# microDriver_v2.net
KiCad netlist of a schematic drawn in EAGLE
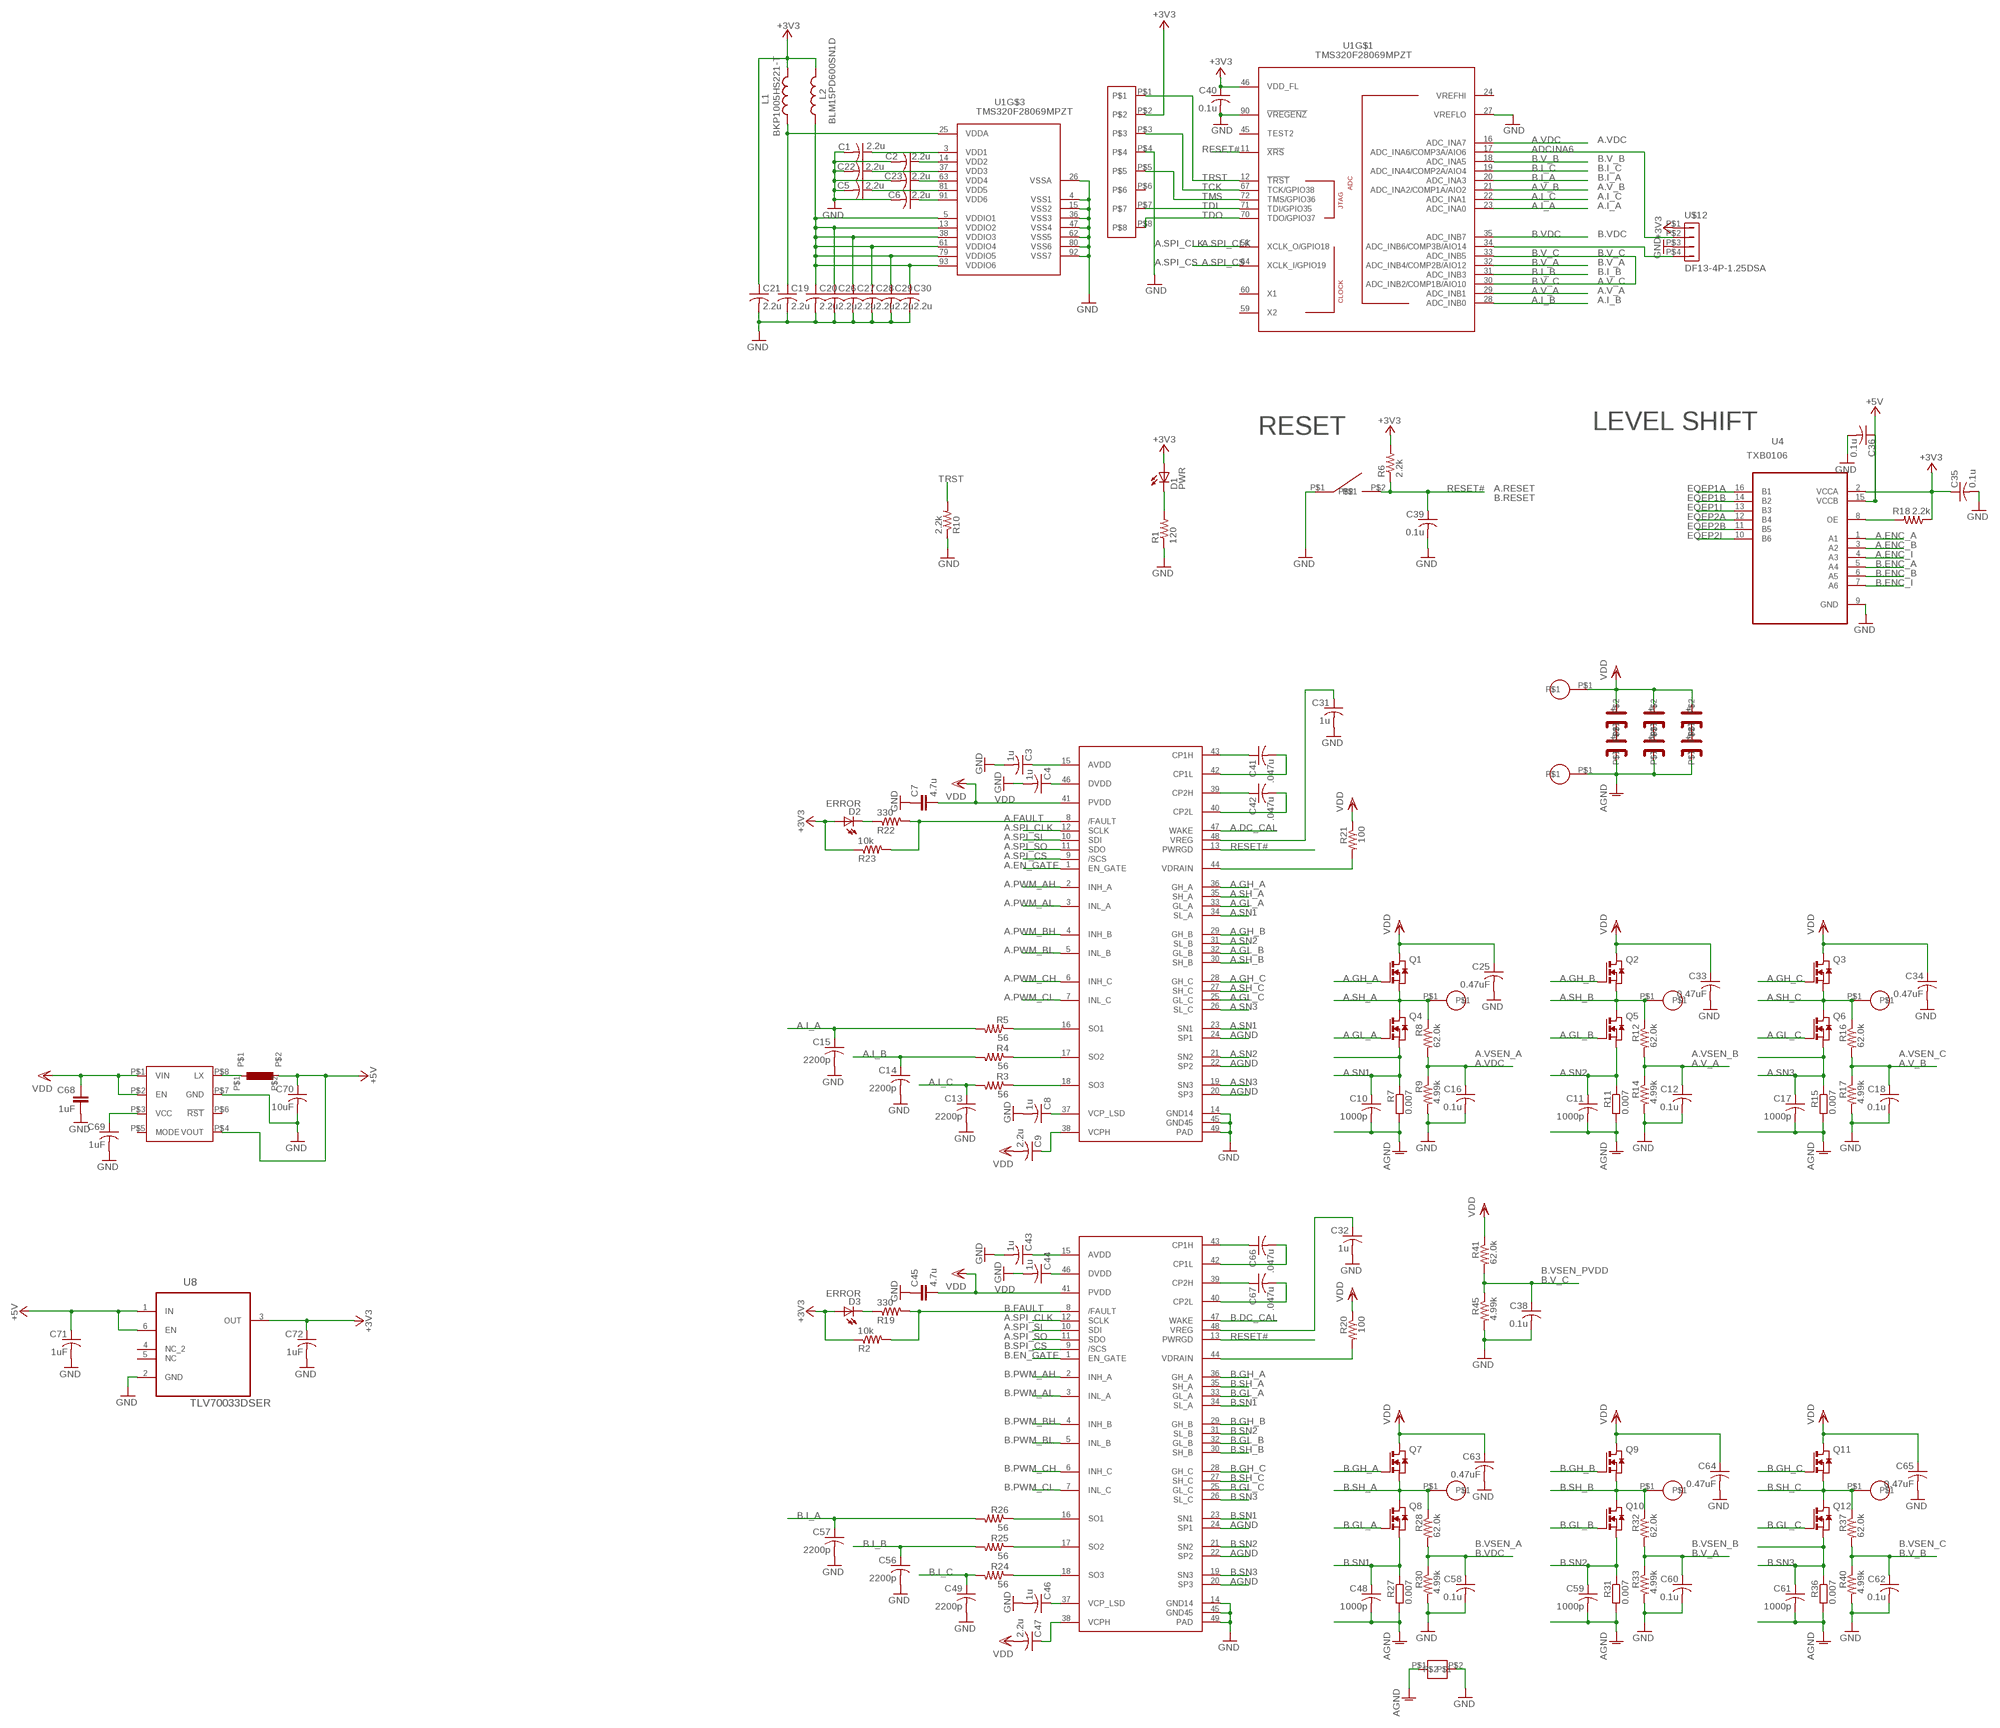
[diagram p0: schematic, sheet 1]
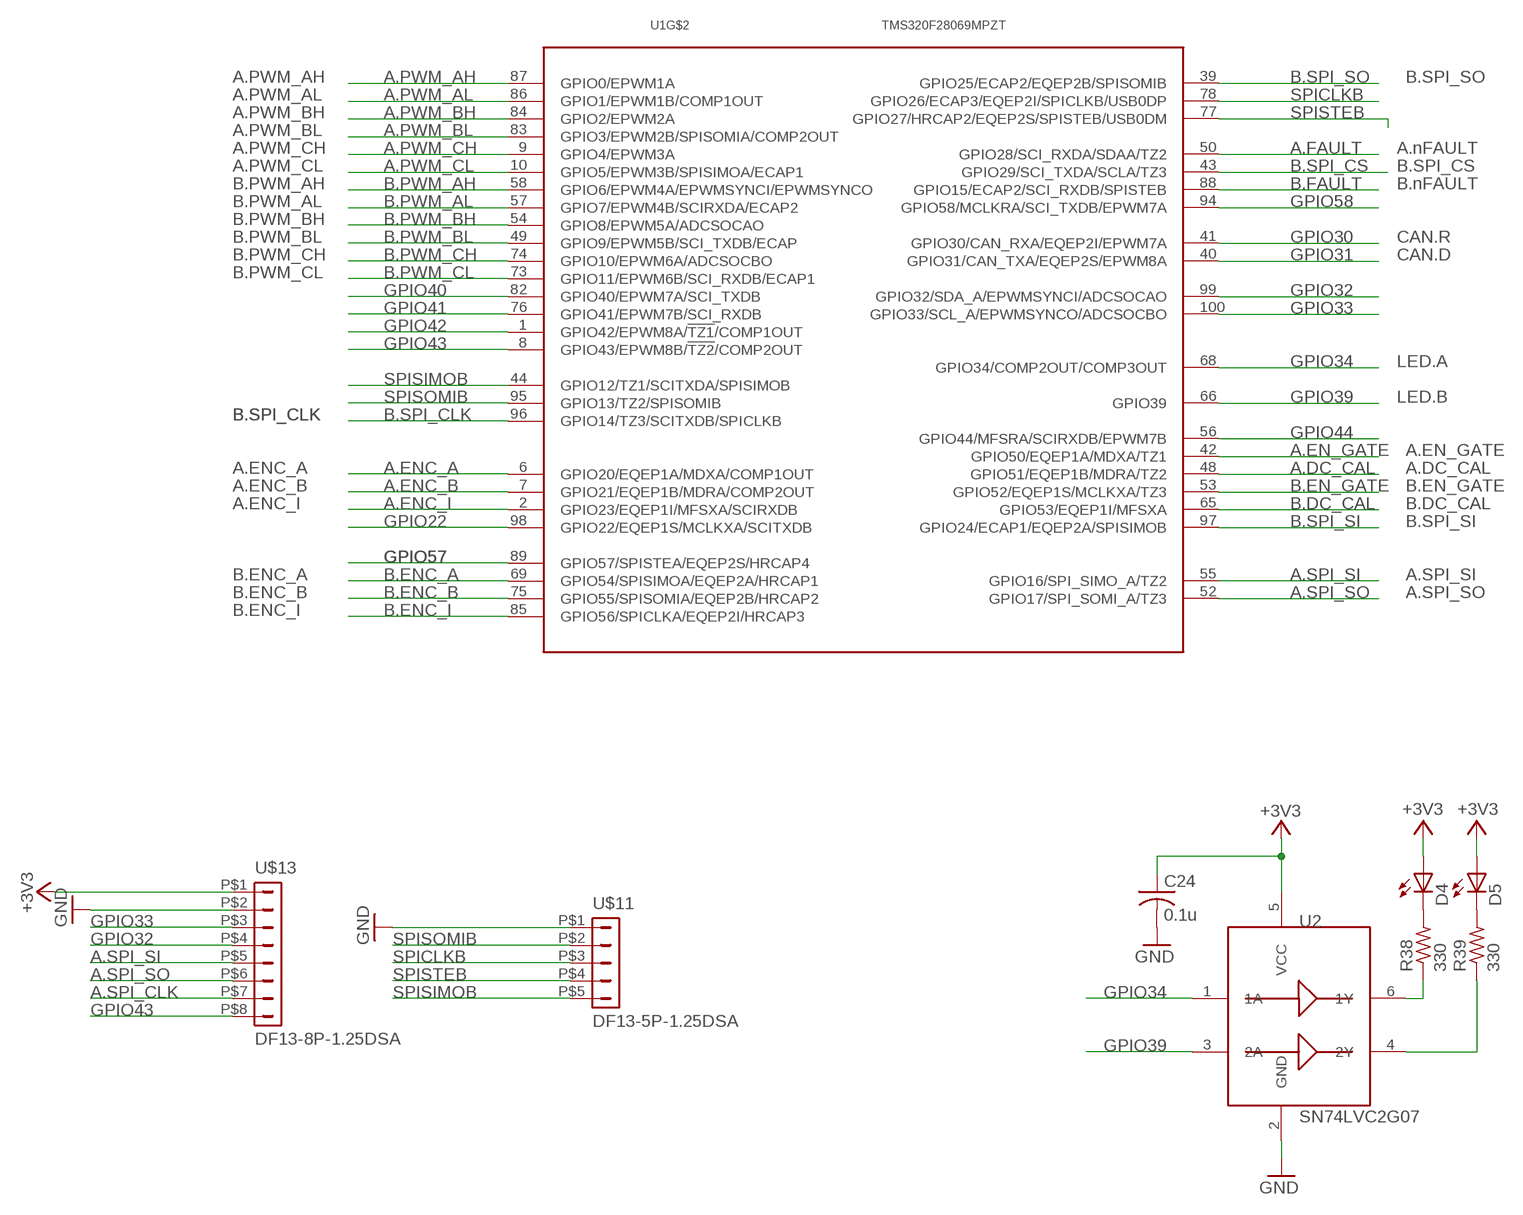
[diagram p1: schematic, sheet 2]
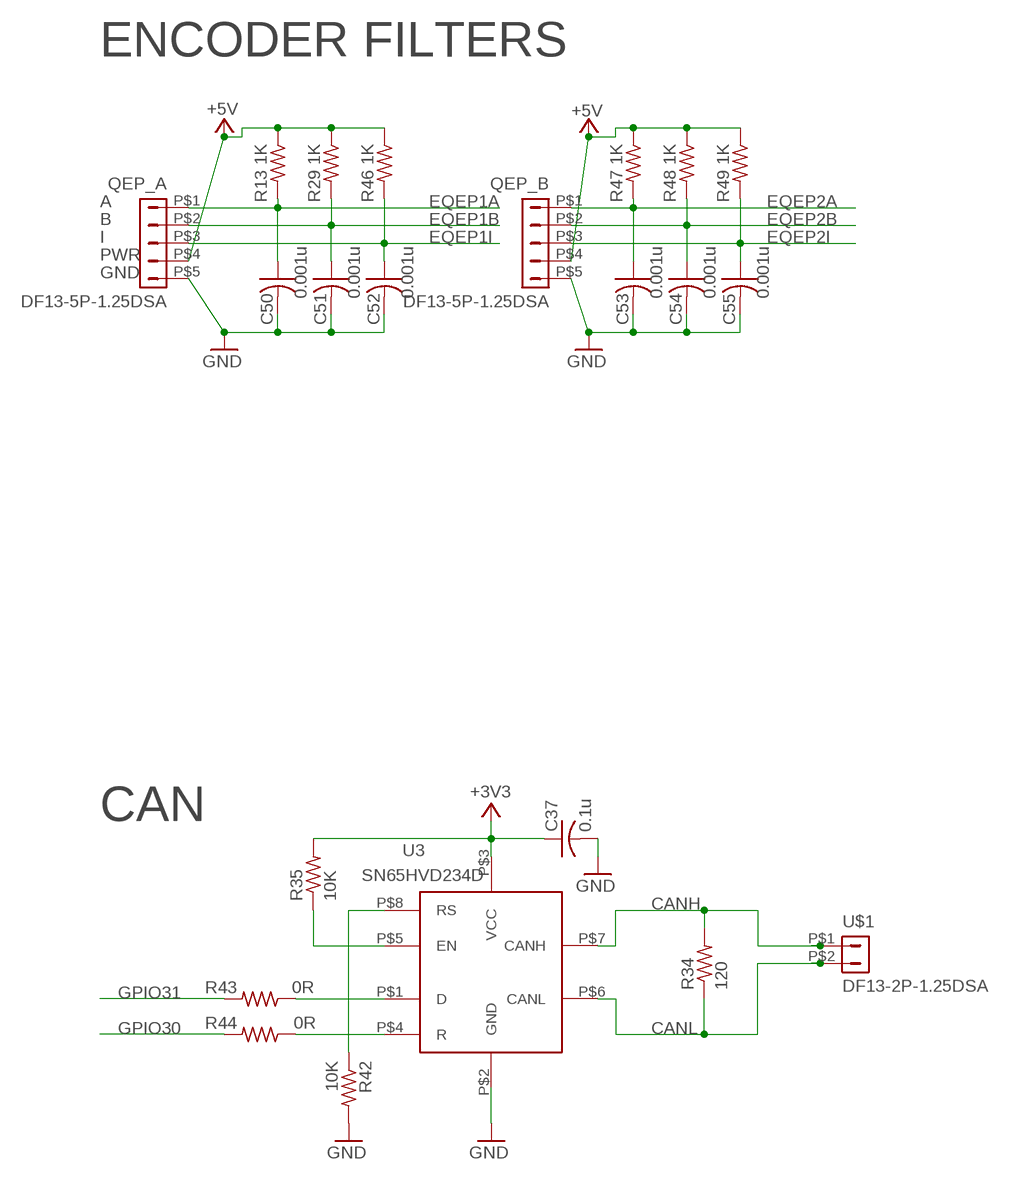
[diagram p2: schematic, sheet 3]

(export (version "E")
  (design (tool "Eeschema 10.0.6"))
  (components
    (comp (ref "C37")
      (value "0.1u")
      (footprint "eagle-import:C0402")
      (libsource (lib "eagle-import") (part "C-USC0402"))
    )
    (comp (ref "C50")
      (value "0.001u")
      (footprint "eagle-import:C0402")
      (libsource (lib "eagle-import") (part "C-USC0402"))
    )
    (comp (ref "C51")
      (value "0.001u")
      (footprint "eagle-import:C0402")
      (libsource (lib "eagle-import") (part "C-USC0402"))
    )
    (comp (ref "C52")
      (value "0.001u")
      (footprint "eagle-import:C0402")
      (libsource (lib "eagle-import") (part "C-USC0402"))
    )
    (comp (ref "C53")
      (value "0.001u")
      (footprint "eagle-import:C0402")
      (libsource (lib "eagle-import") (part "C-USC0402"))
    )
    (comp (ref "C54")
      (value "0.001u")
      (footprint "eagle-import:C0402")
      (libsource (lib "eagle-import") (part "C-USC0402"))
    )
    (comp (ref "C55")
      (value "0.001u")
      (footprint "eagle-import:C0402")
      (libsource (lib "eagle-import") (part "C-USC0402"))
    )
    (comp (ref "QEP_A")
      (value "DF13-5P-1.25DSA")
      (footprint "eagle-import:DF13-5P-1.25DSA")
      (libsource (lib "eagle-import") (part "DF13-5P-1.25DSA"))
    )
    (comp (ref "QEP_B")
      (value "DF13-5P-1.25DSA")
      (footprint "eagle-import:DF13-5P-1.25DSA")
      (libsource (lib "eagle-import") (part "DF13-5P-1.25DSA"))
    )
    (comp (ref "R13")
      (value "1K")
      (footprint "eagle-import:R0402")
      (libsource (lib "eagle-import") (part "R-US_R0402"))
    )
    (comp (ref "R29")
      (value "1K")
      (footprint "eagle-import:R0402")
      (libsource (lib "eagle-import") (part "R-US_R0402"))
    )
    (comp (ref "R34")
      (value "120")
      (footprint "eagle-import:R0402")
      (libsource (lib "eagle-import") (part "R-US_R0402"))
    )
    (comp (ref "R35")
      (value "10K")
      (footprint "eagle-import:R0402")
      (libsource (lib "eagle-import") (part "R-US_R0402"))
    )
    (comp (ref "R42")
      (value "10K")
      (footprint "eagle-import:R0402")
      (libsource (lib "eagle-import") (part "R-US_R0402"))
    )
    (comp (ref "R43")
      (value "0R")
      (footprint "eagle-import:R0402")
      (libsource (lib "eagle-import") (part "R-US_R0402"))
    )
    (comp (ref "R44")
      (value "0R")
      (footprint "eagle-import:R0402")
      (libsource (lib "eagle-import") (part "R-US_R0402"))
    )
    (comp (ref "R46")
      (value "1K")
      (footprint "eagle-import:R0402")
      (libsource (lib "eagle-import") (part "R-US_R0402"))
    )
    (comp (ref "R47")
      (value "1K")
      (footprint "eagle-import:R0402")
      (libsource (lib "eagle-import") (part "R-US_R0402"))
    )
    (comp (ref "R48")
      (value "1K")
      (footprint "eagle-import:R0402")
      (libsource (lib "eagle-import") (part "R-US_R0402"))
    )
    (comp (ref "R49")
      (value "1K")
      (footprint "eagle-import:R0402")
      (libsource (lib "eagle-import") (part "R-US_R0402"))
    )
    (comp (ref "U$1")
      (value "DF13-2P-1.25DSA")
      (footprint "eagle-import:DF13-2P-1.25DSA")
      (libsource (lib "eagle-import") (part "DF13-2P-1.25DSA"))
    )
    (comp (ref "U3")
      (value "SN65HVD234D")
      (footprint "eagle-import:SOIC8-PDSO")
      (libsource (lib "eagle-import") (part "SN65HVD234D"))
    )
    (comp (ref "C24")
      (value "0.1u")
      (footprint "eagle-import:C0402")
      (libsource (lib "eagle-import") (part "C-USC0402"))
    )
    (comp (ref "D4")
      (value "LEDCHIP-LED0603")
      (footprint "eagle-import:CHIP-LED0603")
      (libsource (lib "eagle-import") (part "LEDCHIP-LED0603"))
    )
    (comp (ref "D5")
      (value "LEDCHIP-LED0603")
      (footprint "eagle-import:CHIP-LED0603")
      (libsource (lib "eagle-import") (part "LEDCHIP-LED0603"))
    )
    (comp (ref "R38")
      (value "330")
      (footprint "eagle-import:R0402")
      (libsource (lib "eagle-import") (part "R-US_R0402"))
    )
    (comp (ref "R39")
      (value "330")
      (footprint "eagle-import:R0402")
      (libsource (lib "eagle-import") (part "R-US_R0402"))
    )
    (comp (ref "U$11")
      (value "DF13-5P-1.25DSA")
      (footprint "eagle-import:DF13-5P-1.25DSA")
      (libsource (lib "eagle-import") (part "DF13-5P-1.25DSA"))
    )
    (comp (ref "U$13")
      (value "DF13-8P-1.25DSA")
      (footprint "eagle-import:DF13-8P-1.25DSA")
      (libsource (lib "eagle-import") (part "DF13-8P-1.25DSA"))
    )
    (comp (ref "U1")
      (value "TMS320F28069MPZT")
      (footprint "eagle-import:PQFP100")
      (libsource (lib "eagle-import") (part "TMS320F28069PZSR"))
    )
    (comp (ref "U2")
      (value "SN74LVC2G07")
      (footprint "eagle-import:SOT23-6-DBV")
      (libsource (lib "eagle-import") (part "SN74LVC2G07"))
    )
    (comp (ref "B1")
      (value "B3U")
      (footprint "eagle-import:B3U")
      (libsource (lib "eagle-import") (part "B3U"))
    )
    (comp (ref "C1")
      (value "2.2u")
      (footprint "eagle-import:C0402")
      (libsource (lib "eagle-import") (part "C-USC0402"))
    )
    (comp (ref "C2")
      (value "2.2u")
      (footprint "eagle-import:C0402")
      (libsource (lib "eagle-import") (part "C-USC0402"))
    )
    (comp (ref "C3")
      (value "1u")
      (footprint "eagle-import:C0402")
      (libsource (lib "eagle-import") (part "C-USC0402"))
    )
    (comp (ref "C4")
      (value "1u")
      (footprint "eagle-import:C0402")
      (libsource (lib "eagle-import") (part "C-USC0402"))
    )
    (comp (ref "C5")
      (value "2.2u")
      (footprint "eagle-import:C0402")
      (libsource (lib "eagle-import") (part "C-USC0402"))
    )
    (comp (ref "C6")
      (value "2.2u")
      (footprint "eagle-import:C0402")
      (libsource (lib "eagle-import") (part "C-USC0402"))
    )
    (comp (ref "C7")
      (value "4.7u")
      (footprint "eagle-import:C0805K")
      (libsource (lib "eagle-import") (part "resistor_348_C-EUC0805K"))
    )
    (comp (ref "C8")
      (value "1u")
      (footprint "eagle-import:C0402")
      (libsource (lib "eagle-import") (part "C-USC0402"))
    )
    (comp (ref "C9")
      (value "2.2u")
      (footprint "eagle-import:C0402")
      (libsource (lib "eagle-import") (part "C-USC0402"))
    )
    (comp (ref "C10")
      (value "1000p")
      (footprint "eagle-import:C0402")
      (libsource (lib "eagle-import") (part "C-USC0402"))
    )
    (comp (ref "C11")
      (value "1000p")
      (footprint "eagle-import:C0402")
      (libsource (lib "eagle-import") (part "C-USC0402"))
    )
    (comp (ref "C12")
      (value "0.1u")
      (footprint "eagle-import:C0402")
      (libsource (lib "eagle-import") (part "C-USC0402"))
    )
    (comp (ref "C13")
      (value "2200p")
      (footprint "eagle-import:C0402")
      (libsource (lib "eagle-import") (part "C-USC0402"))
    )
    (comp (ref "C14")
      (value "2200p")
      (footprint "eagle-import:C0402")
      (libsource (lib "eagle-import") (part "C-USC0402"))
    )
    (comp (ref "C15")
      (value "2200p")
      (footprint "eagle-import:C0402")
      (libsource (lib "eagle-import") (part "C-USC0402"))
    )
    (comp (ref "C16")
      (value "0.1u")
      (footprint "eagle-import:C0402")
      (libsource (lib "eagle-import") (part "C-USC0402"))
    )
    (comp (ref "C17")
      (value "1000p")
      (footprint "eagle-import:C0402")
      (libsource (lib "eagle-import") (part "C-USC0402"))
    )
    (comp (ref "C18")
      (value "0.1u")
      (footprint "eagle-import:C0402")
      (libsource (lib "eagle-import") (part "C-USC0402"))
    )
    (comp (ref "C19")
      (value "2.2u")
      (footprint "eagle-import:C0402")
      (libsource (lib "eagle-import") (part "C-USC0402"))
    )
    (comp (ref "C20")
      (value "2.2u")
      (footprint "eagle-import:C0402")
      (libsource (lib "eagle-import") (part "C-USC0402"))
    )
    (comp (ref "C21")
      (value "2.2u")
      (footprint "eagle-import:C0402")
      (libsource (lib "eagle-import") (part "C-USC0402"))
    )
    (comp (ref "C22")
      (value "2.2u")
      (footprint "eagle-import:C0402")
      (libsource (lib "eagle-import") (part "C-USC0402"))
    )
    (comp (ref "C23")
      (value "2.2u")
      (footprint "eagle-import:C0402")
      (libsource (lib "eagle-import") (part "C-USC0402"))
    )
    (comp (ref "C25")
      (value "0.47uF")
      (footprint "eagle-import:C0402")
      (libsource (lib "eagle-import") (part "C-USC0402"))
    )
    (comp (ref "C26")
      (value "2.2u")
      (footprint "eagle-import:C0402")
      (libsource (lib "eagle-import") (part "C-USC0402"))
    )
    (comp (ref "C27")
      (value "2.2u")
      (footprint "eagle-import:C0402")
      (libsource (lib "eagle-import") (part "C-USC0402"))
    )
    (comp (ref "C28")
      (value "2.2u")
      (footprint "eagle-import:C0402")
      (libsource (lib "eagle-import") (part "C-USC0402"))
    )
    (comp (ref "C29")
      (value "2.2u")
      (footprint "eagle-import:C0402")
      (libsource (lib "eagle-import") (part "C-USC0402"))
    )
    (comp (ref "C30")
      (value "2.2u")
      (footprint "eagle-import:C0402")
      (libsource (lib "eagle-import") (part "C-USC0402"))
    )
    (comp (ref "C31")
      (value "1u")
      (footprint "eagle-import:C0402")
      (libsource (lib "eagle-import") (part "C-USC0402"))
    )
    (comp (ref "C32")
      (value "1u")
      (footprint "eagle-import:C0402")
      (libsource (lib "eagle-import") (part "C-USC0402"))
    )
    (comp (ref "C33")
      (value "0.47uF")
      (footprint "eagle-import:C0402")
      (libsource (lib "eagle-import") (part "C-USC0402"))
    )
    (comp (ref "C34")
      (value "0.47uF")
      (footprint "eagle-import:C0402")
      (libsource (lib "eagle-import") (part "C-USC0402"))
    )
    (comp (ref "C35")
      (value "0.1u")
      (footprint "eagle-import:C0402")
      (libsource (lib "eagle-import") (part "C-USC0402"))
    )
    (comp (ref "C36")
      (value "0.1u")
      (footprint "eagle-import:C0402")
      (libsource (lib "eagle-import") (part "C-USC0402"))
    )
    (comp (ref "C38")
      (value "0.1u")
      (footprint "eagle-import:C0402")
      (libsource (lib "eagle-import") (part "C-USC0402"))
    )
    (comp (ref "C39")
      (value "0.1u")
      (footprint "eagle-import:C0402")
      (libsource (lib "eagle-import") (part "C-USC0402"))
    )
    (comp (ref "C40")
      (value "0.1u")
      (footprint "eagle-import:C0402")
      (libsource (lib "eagle-import") (part "C-USC0402"))
    )
    (comp (ref "C41")
      (value ".047u")
      (footprint "eagle-import:C0402")
      (libsource (lib "eagle-import") (part "C-USC0402"))
    )
    (comp (ref "C42")
      (value ".047u")
      (footprint "eagle-import:C0402")
      (libsource (lib "eagle-import") (part "C-USC0402"))
    )
    (comp (ref "C43")
      (value "1u")
      (footprint "eagle-import:C0402")
      (libsource (lib "eagle-import") (part "C-USC0402"))
    )
    (comp (ref "C44")
      (value "1u")
      (footprint "eagle-import:C0402")
      (libsource (lib "eagle-import") (part "C-USC0402"))
    )
    (comp (ref "C45")
      (value "4.7u")
      (footprint "eagle-import:C0805K")
      (libsource (lib "eagle-import") (part "resistor_348_C-EUC0805K"))
    )
    (comp (ref "C46")
      (value "1u")
      (footprint "eagle-import:C0402")
      (libsource (lib "eagle-import") (part "C-USC0402"))
    )
    (comp (ref "C47")
      (value "2.2u")
      (footprint "eagle-import:C0402")
      (libsource (lib "eagle-import") (part "C-USC0402"))
    )
    (comp (ref "C48")
      (value "1000p")
      (footprint "eagle-import:C0402")
      (libsource (lib "eagle-import") (part "C-USC0402"))
    )
    (comp (ref "C49")
      (value "2200p")
      (footprint "eagle-import:C0402")
      (libsource (lib "eagle-import") (part "C-USC0402"))
    )
    (comp (ref "C56")
      (value "2200p")
      (footprint "eagle-import:C0402")
      (libsource (lib "eagle-import") (part "C-USC0402"))
    )
    (comp (ref "C57")
      (value "2200p")
      (footprint "eagle-import:C0402")
      (libsource (lib "eagle-import") (part "C-USC0402"))
    )
    (comp (ref "C58")
      (value "0.1u")
      (footprint "eagle-import:C0402")
      (libsource (lib "eagle-import") (part "C-USC0402"))
    )
    (comp (ref "C59")
      (value "1000p")
      (footprint "eagle-import:C0402")
      (libsource (lib "eagle-import") (part "C-USC0402"))
    )
    (comp (ref "C60")
      (value "0.1u")
      (footprint "eagle-import:C0402")
      (libsource (lib "eagle-import") (part "C-USC0402"))
    )
    (comp (ref "C61")
      (value "1000p")
      (footprint "eagle-import:C0402")
      (libsource (lib "eagle-import") (part "C-USC0402"))
    )
    (comp (ref "C62")
      (value "0.1u")
      (footprint "eagle-import:C0402")
      (libsource (lib "eagle-import") (part "C-USC0402"))
    )
    (comp (ref "C63")
      (value "0.47uF")
      (footprint "eagle-import:C0402")
      (libsource (lib "eagle-import") (part "C-USC0402"))
    )
    (comp (ref "C64")
      (value "0.47uF")
      (footprint "eagle-import:C0402")
      (libsource (lib "eagle-import") (part "C-USC0402"))
    )
    (comp (ref "C65")
      (value "0.47uF")
      (footprint "eagle-import:C0402")
      (libsource (lib "eagle-import") (part "C-USC0402"))
    )
    (comp (ref "C66")
      (value ".047u")
      (footprint "eagle-import:C0402")
      (libsource (lib "eagle-import") (part "C-USC0402"))
    )
    (comp (ref "C67")
      (value ".047u")
      (footprint "eagle-import:C0402")
      (libsource (lib "eagle-import") (part "C-USC0402"))
    )
    (comp (ref "C68")
      (value "1uF")
      (footprint "eagle-import:C0603")
      (libsource (lib "eagle-import") (part "C-EUC0603"))
    )
    (comp (ref "C69")
      (value "1uF")
      (footprint "eagle-import:C0402")
      (libsource (lib "eagle-import") (part "C-USC0402"))
    )
    (comp (ref "C70")
      (value "10uF")
      (footprint "eagle-import:C0402")
      (libsource (lib "eagle-import") (part "C-USC0402"))
    )
    (comp (ref "C71")
      (value "1uF")
      (footprint "eagle-import:C0402")
      (libsource (lib "eagle-import") (part "C-USC0402"))
    )
    (comp (ref "C72")
      (value "1uF")
      (footprint "eagle-import:C0402")
      (libsource (lib "eagle-import") (part "C-USC0402"))
    )
    (comp (ref "D1")
      (value "PWR")
      (footprint "eagle-import:CHIP-LED0603")
      (libsource (lib "eagle-import") (part "LEDCHIP-LED0603"))
    )
    (comp (ref "D2")
      (value "ERROR")
      (footprint "eagle-import:CHIP-LED0603")
      (libsource (lib "eagle-import") (part "LEDCHIP-LED0603"))
    )
    (comp (ref "D3")
      (value "ERROR")
      (footprint "eagle-import:CHIP-LED0603")
      (libsource (lib "eagle-import") (part "LEDCHIP-LED0603"))
    )
    (comp (ref "I1")
      (value "NR4018")
      (footprint "eagle-import:4X4")
      (libsource (lib "eagle-import") (part "NR4018"))
    )
    (comp (ref "L1")
      (value "BKP1005HS221-T")
      (footprint "eagle-import:R0402")
      (libsource (lib "eagle-import") (part "L-US0402"))
    )
    (comp (ref "L2")
      (value "BLM15PD600SN1D")
      (footprint "eagle-import:R0402")
      (libsource (lib "eagle-import") (part "L-US0402"))
    )
    (comp (ref "M1")
      (value "AMP-8")
      (footprint "eagle-import:AMP-MINITEK-8")
      (libsource (lib "eagle-import") (part "AMP-8"))
    )
    (comp (ref "Q1")
      (value "CSD18540")
      (footprint "eagle-import:Q5B")
      (libsource (lib "eagle-import") (part "CSD18540"))
    )
    (comp (ref "Q2")
      (value "CSD18540")
      (footprint "eagle-import:Q5B")
      (libsource (lib "eagle-import") (part "CSD18540"))
    )
    (comp (ref "Q3")
      (value "CSD18540")
      (footprint "eagle-import:Q5B")
      (libsource (lib "eagle-import") (part "CSD18540"))
    )
    (comp (ref "Q4")
      (value "CSD18540")
      (footprint "eagle-import:Q5B")
      (libsource (lib "eagle-import") (part "CSD18540"))
    )
    (comp (ref "Q5")
      (value "CSD18540")
      (footprint "eagle-import:Q5B")
      (libsource (lib "eagle-import") (part "CSD18540"))
    )
    (comp (ref "Q6")
      (value "CSD18540")
      (footprint "eagle-import:Q5B")
      (libsource (lib "eagle-import") (part "CSD18540"))
    )
    (comp (ref "Q7")
      (value "CSD18540")
      (footprint "eagle-import:Q5B")
      (libsource (lib "eagle-import") (part "CSD18540"))
    )
    (comp (ref "Q8")
      (value "CSD18540")
      (footprint "eagle-import:Q5B")
      (libsource (lib "eagle-import") (part "CSD18540"))
    )
    (comp (ref "Q9")
      (value "CSD18540")
      (footprint "eagle-import:Q5B")
      (libsource (lib "eagle-import") (part "CSD18540"))
    )
    (comp (ref "Q10")
      (value "CSD18540")
      (footprint "eagle-import:Q5B")
      (libsource (lib "eagle-import") (part "CSD18540"))
    )
    (comp (ref "Q11")
      (value "CSD18540")
      (footprint "eagle-import:Q5B")
      (libsource (lib "eagle-import") (part "CSD18540"))
    )
    (comp (ref "Q12")
      (value "CSD18540")
      (footprint "eagle-import:Q5B")
      (libsource (lib "eagle-import") (part "CSD18540"))
    )
    (comp (ref "R1")
      (value "120")
      (footprint "eagle-import:R0402")
      (libsource (lib "eagle-import") (part "R-US_R0402"))
    )
    (comp (ref "R2")
      (value "10k")
      (footprint "eagle-import:R0402")
      (libsource (lib "eagle-import") (part "R-US_R0402"))
    )
    (comp (ref "R3")
      (value "56")
      (footprint "eagle-import:R0402")
      (libsource (lib "eagle-import") (part "R-US_R0402"))
    )
    (comp (ref "R4")
      (value "56")
      (footprint "eagle-import:R0402")
      (libsource (lib "eagle-import") (part "R-US_R0402"))
    )
    (comp (ref "R5")
      (value "56")
      (footprint "eagle-import:R0402")
      (libsource (lib "eagle-import") (part "R-US_R0402"))
    )
    (comp (ref "R6")
      (value "2.2k")
      (footprint "eagle-import:R0402")
      (libsource (lib "eagle-import") (part "R-US_R0402"))
    )
    (comp (ref "R7")
      (value "0.007")
      (footprint "eagle-import:R2512")
      (libsource (lib "eagle-import") (part "R-EU_R2512"))
    )
    (comp (ref "R8")
      (value "62.0k")
      (footprint "eagle-import:R0402")
      (libsource (lib "eagle-import") (part "R-US_R0402"))
    )
    (comp (ref "R9")
      (value "4.99k")
      (footprint "eagle-import:R0402")
      (libsource (lib "eagle-import") (part "R-US_R0402"))
    )
    (comp (ref "R10")
      (value "2.2k")
      (footprint "eagle-import:R0402")
      (libsource (lib "eagle-import") (part "R-US_R0402"))
    )
    (comp (ref "R11")
      (value "0.007")
      (footprint "eagle-import:R2512")
      (libsource (lib "eagle-import") (part "R-EU_R2512"))
    )
    (comp (ref "R12")
      (value "62.0k")
      (footprint "eagle-import:R0402")
      (libsource (lib "eagle-import") (part "R-US_R0402"))
    )
    (comp (ref "R14")
      (value "4.99k")
      (footprint "eagle-import:R0402")
      (libsource (lib "eagle-import") (part "R-US_R0402"))
    )
    (comp (ref "R15")
      (value "0.007")
      (footprint "eagle-import:R2512")
      (libsource (lib "eagle-import") (part "R-EU_R2512"))
    )
    (comp (ref "R16")
      (value "62.0k")
      (footprint "eagle-import:R0402")
      (libsource (lib "eagle-import") (part "R-US_R0402"))
    )
    (comp (ref "R17")
      (value "4.99k")
      (footprint "eagle-import:R0402")
      (libsource (lib "eagle-import") (part "R-US_R0402"))
    )
    (comp (ref "R18")
      (value "2.2k")
      (footprint "eagle-import:R0402")
      (libsource (lib "eagle-import") (part "R-US_R0402"))
    )
    (comp (ref "R19")
      (value "330")
      (footprint "eagle-import:R0402")
      (libsource (lib "eagle-import") (part "R-US_R0402"))
    )
    (comp (ref "R20")
      (value "100")
      (footprint "eagle-import:R0402")
      (libsource (lib "eagle-import") (part "R-US_R0402"))
    )
    (comp (ref "R21")
      (value "100")
      (footprint "eagle-import:R0402")
      (libsource (lib "eagle-import") (part "R-US_R0402"))
    )
    (comp (ref "R22")
      (value "330")
      (footprint "eagle-import:R0402")
      (libsource (lib "eagle-import") (part "R-US_R0402"))
    )
    (comp (ref "R23")
      (value "10k")
      (footprint "eagle-import:R0402")
      (libsource (lib "eagle-import") (part "R-US_R0402"))
    )
    (comp (ref "R24")
      (value "56")
      (footprint "eagle-import:R0402")
      (libsource (lib "eagle-import") (part "R-US_R0402"))
    )
    (comp (ref "R25")
      (value "56")
      (footprint "eagle-import:R0402")
      (libsource (lib "eagle-import") (part "R-US_R0402"))
    )
    (comp (ref "R26")
      (value "56")
      (footprint "eagle-import:R0402")
      (libsource (lib "eagle-import") (part "R-US_R0402"))
    )
    (comp (ref "R27")
      (value "0.007")
      (footprint "eagle-import:R2512")
      (libsource (lib "eagle-import") (part "R-EU_R2512"))
    )
    (comp (ref "R28")
      (value "62.0k")
      (footprint "eagle-import:R0402")
      (libsource (lib "eagle-import") (part "R-US_R0402"))
    )
    (comp (ref "R30")
      (value "4.99k")
      (footprint "eagle-import:R0402")
      (libsource (lib "eagle-import") (part "R-US_R0402"))
    )
    (comp (ref "R31")
      (value "0.007")
      (footprint "eagle-import:R2512")
      (libsource (lib "eagle-import") (part "R-EU_R2512"))
    )
    (comp (ref "R32")
      (value "62.0k")
      (footprint "eagle-import:R0402")
      (libsource (lib "eagle-import") (part "R-US_R0402"))
    )
    (comp (ref "R33")
      (value "4.99k")
      (footprint "eagle-import:R0402")
      (libsource (lib "eagle-import") (part "R-US_R0402"))
    )
    (comp (ref "R36")
      (value "0.007")
      (footprint "eagle-import:R2512")
      (libsource (lib "eagle-import") (part "R-EU_R2512"))
    )
    (comp (ref "R37")
      (value "62.0k")
      (footprint "eagle-import:R0402")
      (libsource (lib "eagle-import") (part "R-US_R0402"))
    )
    (comp (ref "R40")
      (value "4.99k")
      (footprint "eagle-import:R0402")
      (libsource (lib "eagle-import") (part "R-US_R0402"))
    )
    (comp (ref "R41")
      (value "62.0k")
      (footprint "eagle-import:R0402")
      (libsource (lib "eagle-import") (part "R-US_R0402"))
    )
    (comp (ref "R45")
      (value "4.99k")
      (footprint "eagle-import:R0402")
      (libsource (lib "eagle-import") (part "R-US_R0402"))
    )
    (comp (ref "T1")
      (value "7343-CAP")
      (footprint "eagle-import:M7343-CAP")
      (libsource (lib "eagle-import") (part "7343-CAP"))
    )
    (comp (ref "T2")
      (value "7343-CAP")
      (footprint "eagle-import:M7343-CAP")
      (libsource (lib "eagle-import") (part "7343-CAP"))
    )
    (comp (ref "T3")
      (value "7343-CAP")
      (footprint "eagle-import:M7343-CAP")
      (libsource (lib "eagle-import") (part "7343-CAP"))
    )
    (comp (ref "T4")
      (value "7343-CAP")
      (footprint "eagle-import:M7343-CAP")
      (libsource (lib "eagle-import") (part "7343-CAP"))
    )
    (comp (ref "T5")
      (value "7343-CAP")
      (footprint "eagle-import:M7343-CAP")
      (libsource (lib "eagle-import") (part "7343-CAP"))
    )
    (comp (ref "T6")
      (value "7343-CAP")
      (footprint "eagle-import:M7343-CAP")
      (libsource (lib "eagle-import") (part "7343-CAP"))
    )
    (comp (ref "U$2")
      (value "GND-AGND")
      (footprint "eagle-import:GND-AGND")
      (libsource (lib "eagle-import") (part "GND-AGND"))
    )
    (comp (ref "U$3")
      (value "BLDC_PAD")
      (footprint "eagle-import:BLDC_PAD")
      (libsource (lib "eagle-import") (part "BLDC_PAD"))
    )
    (comp (ref "U$4")
      (value "BLDC_PAD")
      (footprint "eagle-import:BLDC_PAD")
      (libsource (lib "eagle-import") (part "BLDC_PAD"))
    )
    (comp (ref "U$5")
      (value "BLDC_PAD")
      (footprint "eagle-import:BLDC_PAD")
      (libsource (lib "eagle-import") (part "BLDC_PAD"))
    )
    (comp (ref "U$6")
      (value "BLDC_PAD")
      (footprint "eagle-import:BLDC_PAD")
      (libsource (lib "eagle-import") (part "BLDC_PAD"))
    )
    (comp (ref "U$7")
      (value "BLDC_PAD")
      (footprint "eagle-import:BLDC_PAD")
      (libsource (lib "eagle-import") (part "BLDC_PAD"))
    )
    (comp (ref "U$8")
      (value "BLDC_PAD")
      (footprint "eagle-import:BLDC_PAD")
      (libsource (lib "eagle-import") (part "BLDC_PAD"))
    )
    (comp (ref "U$9")
      (value "BLDC_PAD")
      (footprint "eagle-import:BLDC_PAD")
      (libsource (lib "eagle-import") (part "BLDC_PAD"))
    )
    (comp (ref "U$10")
      (value "BLDC_PAD")
      (footprint "eagle-import:BLDC_PAD")
      (libsource (lib "eagle-import") (part "BLDC_PAD"))
    )
    (comp (ref "U$12")
      (value "DF13-4P-1.25DSA")
      (footprint "eagle-import:DF13-4P-1.25DSA")
      (libsource (lib "eagle-import") (part "DF13-4P-1.25DSA"))
    )
    (comp (ref "U4")
      (value "TXB0106")
      (footprint "eagle-import:VQFN-N16")
      (libsource (lib "eagle-import") (part "TXB0106"))
    )
    (comp (ref "U5")
      (value "DRV8305")
      (footprint "eagle-import:HTQFP-48")
      (libsource (lib "eagle-import") (part "DRV8305"))
    )
    (comp (ref "U6")
      (value "DRV8305")
      (footprint "eagle-import:HTQFP-48")
      (libsource (lib "eagle-import") (part "DRV8305"))
    )
    (comp (ref "U7")
      (value "MAX15062")
      (footprint "eagle-import:TDFN-8")
      (libsource (lib "eagle-import") (part "MAX15062"))
    )
    (comp (ref "U8")
      (value "TLV70033DSER")
      (footprint "eagle-import:SON50P150X150X80-6N")
      (libsource (lib "eagle-import") (part "TLV70033DSER"))
    )
  )
  (nets
    (net (code "1") (name "+3V3") (class "Default")
      (node (ref "C21") (pin "1") (pinfunction "1_1") (pintype "passive"))
      (node (ref "C24") (pin "1") (pinfunction "1_1") (pintype "passive"))
      (node (ref "C35") (pin "1") (pinfunction "1_1") (pintype "passive"))
      (node (ref "C37") (pin "1") (pinfunction "1_1") (pintype "passive"))
      (node (ref "C40") (pin "1") (pinfunction "1_1") (pintype "passive"))
      (node (ref "C72") (pin "1") (pinfunction "1_1") (pintype "passive"))
      (node (ref "D1") (pin "A") (pinfunction "A_A") (pintype "passive"))
      (node (ref "D2") (pin "A") (pinfunction "A_A") (pintype "passive"))
      (node (ref "D3") (pin "A") (pinfunction "A_A") (pintype "passive"))
      (node (ref "D4") (pin "A") (pinfunction "A_A") (pintype "passive"))
      (node (ref "D5") (pin "A") (pinfunction "A_A") (pintype "passive"))
      (node (ref "L1") (pin "2") (pinfunction "2_2") (pintype "passive"))
      (node (ref "L2") (pin "2") (pinfunction "2_2") (pintype "passive"))
      (node (ref "M1") (pin "P$2") (pinfunction "P$2_P$2") (pintype "bidirectional"))
      (node (ref "R18") (pin "1") (pinfunction "1_1") (pintype "passive"))
      (node (ref "R2") (pin "1") (pinfunction "1_1") (pintype "passive"))
      (node (ref "R23") (pin "1") (pinfunction "1_1") (pintype "passive"))
      (node (ref "R35") (pin "2") (pinfunction "2_2") (pintype "passive"))
      (node (ref "R6") (pin "2") (pinfunction "2_2") (pintype "passive"))
      (node (ref "U$12") (pin "P$1") (pinfunction "1_P$1") (pintype "passive"))
      (node (ref "U$13") (pin "P$1") (pinfunction "1_P$1") (pintype "passive"))
      (node (ref "U1") (pin "46") (pinfunction "VDD_FL_46") (pintype "power_in"))
      (node (ref "U2") (pin "5") (pinfunction "VCC_5") (pintype "bidirectional"))
      (node (ref "U3") (pin "P$3") (pinfunction "VCC_P$3") (pintype "bidirectional"))
      (node (ref "U4") (pin "2") (pinfunction "VCCA_2") (pintype "power_in"))
      (node (ref "U8") (pin "3") (pinfunction "OUT_3") (pintype "output"))
    )
    (net (code "2") (name "+5V") (class "Default")
      (node (ref "C36") (pin "1") (pinfunction "1_1") (pintype "passive"))
      (node (ref "C70") (pin "1") (pinfunction "1_1") (pintype "passive"))
      (node (ref "C71") (pin "1") (pinfunction "1_1") (pintype "passive"))
      (node (ref "I1") (pin "P$2") (pinfunction "P$2_P$2") (pintype "bidirectional"))
      (node (ref "QEP_A") (pin "P$4") (pinfunction "4_P$4") (pintype "passive"))
      (node (ref "QEP_B") (pin "P$4") (pinfunction "4_P$4") (pintype "passive"))
      (node (ref "R13") (pin "1") (pinfunction "1_1") (pintype "passive"))
      (node (ref "R29") (pin "1") (pinfunction "1_1") (pintype "passive"))
      (node (ref "R46") (pin "1") (pinfunction "1_1") (pintype "passive"))
      (node (ref "R47") (pin "1") (pinfunction "1_1") (pintype "passive"))
      (node (ref "R48") (pin "1") (pinfunction "1_1") (pintype "passive"))
      (node (ref "R49") (pin "1") (pinfunction "1_1") (pintype "passive"))
      (node (ref "U4") (pin "15") (pinfunction "VCCB_15") (pintype "power_in"))
      (node (ref "U7") (pin "P$4") (pinfunction "VOUT_P$4") (pintype "bidirectional"))
      (node (ref "U8") (pin "1") (pinfunction "IN_1") (pintype "power_in"))
      (node (ref "U8") (pin "6") (pinfunction "EN_6") (pintype "input"))
    )
    (net (code "3") (name "A.DC_CAL") (class "Default")
      (node (ref "U1") (pin "48") (pinfunction "GPIO51/EQEP1B/MDRA/TZ2_48") (pintype "bidirectional"))
      (node (ref "U6") (pin "47") (pinfunction "WAKE_47") (pintype "bidirectional"))
    )
    (net (code "4") (name "A.ENC_A") (class "Default")
      (node (ref "U1") (pin "6") (pinfunction "GPIO20/EQEP1A/MDXA/COMP1OUT_6") (pintype "bidirectional"))
      (node (ref "U4") (pin "1") (pinfunction "A1_1") (pintype "bidirectional"))
    )
    (net (code "5") (name "A.ENC_B") (class "Default")
      (node (ref "U1") (pin "7") (pinfunction "GPIO21/EQEP1B/MDRA/COMP2OUT_7") (pintype "bidirectional"))
      (node (ref "U4") (pin "3") (pinfunction "A2_3") (pintype "bidirectional"))
    )
    (net (code "6") (name "A.ENC_I") (class "Default")
      (node (ref "U1") (pin "2") (pinfunction "GPIO23/EQEP1I/MFSXA/SCIRXDB_2") (pintype "bidirectional"))
      (node (ref "U4") (pin "4") (pinfunction "A3_4") (pintype "bidirectional"))
    )
    (net (code "7") (name "A.EN_GATE") (class "Default")
      (node (ref "U1") (pin "42") (pinfunction "GPIO50/EQEP1A/MDXA/TZ1_42") (pintype "bidirectional"))
      (node (ref "U6") (pin "1") (pinfunction "EN_GATE_1") (pintype "bidirectional"))
    )
    (net (code "8") (name "A.FAULT") (class "Default")
      (node (ref "R22") (pin "2") (pinfunction "2_2") (pintype "passive"))
      (node (ref "R23") (pin "2") (pinfunction "2_2") (pintype "passive"))
      (node (ref "U1") (pin "50") (pinfunction "GPIO28/SCI_RXDA/SDAA/TZ2_50") (pintype "bidirectional"))
      (node (ref "U6") (pin "8") (pinfunction "/FAULT_8") (pintype "bidirectional"))
    )
    (net (code "9") (name "A.GH_A") (class "Default")
      (node (ref "Q1") (pin "4") (pinfunction "G_4") (pintype "passive"))
      (node (ref "U6") (pin "36") (pinfunction "GH_A_36") (pintype "bidirectional"))
    )
    (net (code "10") (name "A.GH_B") (class "Default")
      (node (ref "Q2") (pin "4") (pinfunction "G_4") (pintype "passive"))
      (node (ref "U6") (pin "29") (pinfunction "GH_B_29") (pintype "bidirectional"))
    )
    (net (code "11") (name "A.GH_C") (class "Default")
      (node (ref "Q3") (pin "4") (pinfunction "G_4") (pintype "passive"))
      (node (ref "U6") (pin "28") (pinfunction "GH_C_28") (pintype "bidirectional"))
    )
    (net (code "12") (name "A.GL_A") (class "Default")
      (node (ref "Q4") (pin "4") (pinfunction "G_4") (pintype "passive"))
      (node (ref "U6") (pin "33") (pinfunction "GL_A_33") (pintype "bidirectional"))
    )
    (net (code "13") (name "A.GL_B") (class "Default")
      (node (ref "Q5") (pin "4") (pinfunction "G_4") (pintype "passive"))
      (node (ref "U6") (pin "32") (pinfunction "GL_B_32") (pintype "bidirectional"))
    )
    (net (code "14") (name "A.GL_C") (class "Default")
      (node (ref "Q6") (pin "4") (pinfunction "G_4") (pintype "passive"))
      (node (ref "U6") (pin "25") (pinfunction "GL_C_25") (pintype "bidirectional"))
    )
    (net (code "15") (name "A.I_A") (class "Default")
      (node (ref "C15") (pin "1") (pinfunction "1_1") (pintype "passive"))
      (node (ref "R5") (pin "2") (pinfunction "2_2") (pintype "passive"))
      (node (ref "U1") (pin "23") (pinfunction "ADC_INA0_23") (pintype "input"))
    )
    (net (code "16") (name "A.I_B") (class "Default")
      (node (ref "C14") (pin "1") (pinfunction "1_1") (pintype "passive"))
      (node (ref "R4") (pin "2") (pinfunction "2_2") (pintype "passive"))
      (node (ref "U1") (pin "28") (pinfunction "ADC_INB0_28") (pintype "input"))
    )
    (net (code "17") (name "A.I_C") (class "Default")
      (node (ref "C13") (pin "1") (pinfunction "1_1") (pintype "passive"))
      (node (ref "R3") (pin "2") (pinfunction "2_2") (pintype "passive"))
      (node (ref "U1") (pin "22") (pinfunction "ADC_INA1_22") (pintype "input"))
    )
    (net (code "18") (name "A.PWM_AH") (class "Default")
      (node (ref "U1") (pin "87") (pinfunction "GPIO0/EPWM1A_87") (pintype "bidirectional"))
      (node (ref "U6") (pin "2") (pinfunction "INH_A_2") (pintype "bidirectional"))
    )
    (net (code "19") (name "A.PWM_AL") (class "Default")
      (node (ref "U1") (pin "86") (pinfunction "GPIO1/EPWM1B/COMP1OUT_86") (pintype "bidirectional"))
      (node (ref "U6") (pin "3") (pinfunction "INL_A_3") (pintype "bidirectional"))
    )
    (net (code "20") (name "A.PWM_BH") (class "Default")
      (node (ref "U1") (pin "84") (pinfunction "GPIO2/EPWM2A_84") (pintype "bidirectional"))
      (node (ref "U6") (pin "4") (pinfunction "INH_B_4") (pintype "bidirectional"))
    )
    (net (code "21") (name "A.PWM_BL") (class "Default")
      (node (ref "U1") (pin "83") (pinfunction "GPIO3/EPWM2B/SPISOMIA/COMP2OUT_83") (pintype "bidirectional"))
      (node (ref "U6") (pin "5") (pinfunction "INL_B_5") (pintype "bidirectional"))
    )
    (net (code "22") (name "A.PWM_CH") (class "Default")
      (node (ref "U1") (pin "9") (pinfunction "GPIO4/EPWM3A_9") (pintype "bidirectional"))
      (node (ref "U6") (pin "6") (pinfunction "INH_C_6") (pintype "bidirectional"))
    )
    (net (code "23") (name "A.PWM_CL") (class "Default")
      (node (ref "U1") (pin "10") (pinfunction "GPIO5/EPWM3B/SPISIMOA/ECAP1_10") (pintype "bidirectional"))
      (node (ref "U6") (pin "7") (pinfunction "INL_C_7") (pintype "bidirectional"))
    )
    (net (code "24") (name "A.SH_A") (class "Default")
      (node (ref "Q1") (pin "1") (pinfunction "S_1") (pintype "passive"))
      (node (ref "Q1") (pin "2") (pinfunction "S_2") (pintype "passive"))
      (node (ref "Q1") (pin "3") (pinfunction "S_3") (pintype "passive"))
      (node (ref "Q4") (pin "5") (pinfunction "D_5") (pintype "passive"))
      (node (ref "Q4") (pin "6") (pinfunction "D_6") (pintype "passive"))
      (node (ref "Q4") (pin "7") (pinfunction "D_7") (pintype "passive"))
      (node (ref "Q4") (pin "8") (pinfunction "D_8") (pintype "passive"))
      (node (ref "Q4") (pin "9") (pinfunction "D_9") (pintype "passive"))
      (node (ref "R8") (pin "1") (pinfunction "1_1") (pintype "passive"))
      (node (ref "U$6") (pin "P$1") (pinfunction "P$1_P$1") (pintype "bidirectional"))
      (node (ref "U6") (pin "35") (pinfunction "SH_A_35") (pintype "bidirectional"))
    )
    (net (code "25") (name "A.SH_B") (class "Default")
      (node (ref "Q2") (pin "1") (pinfunction "S_1") (pintype "passive"))
      (node (ref "Q2") (pin "2") (pinfunction "S_2") (pintype "passive"))
      (node (ref "Q2") (pin "3") (pinfunction "S_3") (pintype "passive"))
      (node (ref "Q5") (pin "5") (pinfunction "D_5") (pintype "passive"))
      (node (ref "Q5") (pin "6") (pinfunction "D_6") (pintype "passive"))
      (node (ref "Q5") (pin "7") (pinfunction "D_7") (pintype "passive"))
      (node (ref "Q5") (pin "8") (pinfunction "D_8") (pintype "passive"))
      (node (ref "Q5") (pin "9") (pinfunction "D_9") (pintype "passive"))
      (node (ref "R12") (pin "1") (pinfunction "1_1") (pintype "passive"))
      (node (ref "U$7") (pin "P$1") (pinfunction "P$1_P$1") (pintype "bidirectional"))
      (node (ref "U6") (pin "30") (pinfunction "SH_B_30") (pintype "bidirectional"))
    )
    (net (code "26") (name "A.SH_C") (class "Default")
      (node (ref "Q3") (pin "1") (pinfunction "S_1") (pintype "passive"))
      (node (ref "Q3") (pin "2") (pinfunction "S_2") (pintype "passive"))
      (node (ref "Q3") (pin "3") (pinfunction "S_3") (pintype "passive"))
      (node (ref "Q6") (pin "5") (pinfunction "D_5") (pintype "passive"))
      (node (ref "Q6") (pin "6") (pinfunction "D_6") (pintype "passive"))
      (node (ref "Q6") (pin "7") (pinfunction "D_7") (pintype "passive"))
      (node (ref "Q6") (pin "8") (pinfunction "D_8") (pintype "passive"))
      (node (ref "Q6") (pin "9") (pinfunction "D_9") (pintype "passive"))
      (node (ref "R16") (pin "1") (pinfunction "1_1") (pintype "passive"))
      (node (ref "U$8") (pin "P$1") (pinfunction "P$1_P$1") (pintype "bidirectional"))
      (node (ref "U6") (pin "27") (pinfunction "SH_C_27") (pintype "bidirectional"))
    )
    (net (code "27") (name "A.SN1") (class "Default")
      (node (ref "C10") (pin "1") (pinfunction "1_1") (pintype "passive"))
      (node (ref "Q4") (pin "1") (pinfunction "S_1") (pintype "passive"))
      (node (ref "Q4") (pin "2") (pinfunction "S_2") (pintype "passive"))
      (node (ref "Q4") (pin "3") (pinfunction "S_3") (pintype "passive"))
      (node (ref "R7") (pin "1") (pinfunction "1_1") (pintype "passive"))
      (node (ref "U6") (pin "23") (pinfunction "SN1_23") (pintype "bidirectional"))
      (node (ref "U6") (pin "34") (pinfunction "SL_A_34") (pintype "bidirectional"))
    )
    (net (code "28") (name "A.SN2") (class "Default")
      (node (ref "C11") (pin "1") (pinfunction "1_1") (pintype "passive"))
      (node (ref "Q5") (pin "1") (pinfunction "S_1") (pintype "passive"))
      (node (ref "Q5") (pin "2") (pinfunction "S_2") (pintype "passive"))
      (node (ref "Q5") (pin "3") (pinfunction "S_3") (pintype "passive"))
      (node (ref "R11") (pin "1") (pinfunction "1_1") (pintype "passive"))
      (node (ref "U6") (pin "21") (pinfunction "SN2_21") (pintype "bidirectional"))
      (node (ref "U6") (pin "31") (pinfunction "SL_B_31") (pintype "bidirectional"))
    )
    (net (code "29") (name "A.SN3") (class "Default")
      (node (ref "C17") (pin "1") (pinfunction "1_1") (pintype "passive"))
      (node (ref "Q6") (pin "1") (pinfunction "S_1") (pintype "passive"))
      (node (ref "Q6") (pin "2") (pinfunction "S_2") (pintype "passive"))
      (node (ref "Q6") (pin "3") (pinfunction "S_3") (pintype "passive"))
      (node (ref "R15") (pin "1") (pinfunction "1_1") (pintype "passive"))
      (node (ref "U6") (pin "19") (pinfunction "SN3_19") (pintype "bidirectional"))
      (node (ref "U6") (pin "26") (pinfunction "SL_C_26") (pintype "bidirectional"))
    )
    (net (code "30") (name "A.SPI_CLK") (class "Default")
      (node (ref "U$13") (pin "P$7") (pinfunction "7_P$7") (pintype "passive"))
      (node (ref "U1") (pin "51") (pinfunction "XCLK_O/GPIO18_51") (pintype "output"))
      (node (ref "U5") (pin "12") (pinfunction "SCLK_12") (pintype "bidirectional"))
      (node (ref "U6") (pin "12") (pinfunction "SCLK_12") (pintype "bidirectional"))
    )
    (net (code "31") (name "A.SPI_CS") (class "Default")
      (node (ref "U1") (pin "64") (pinfunction "XCLK_I/GPIO19_64") (pintype "input"))
      (node (ref "U6") (pin "9") (pinfunction "/SCS_9") (pintype "bidirectional"))
    )
    (net (code "32") (name "A.SPI_SI") (class "Default")
      (node (ref "U$13") (pin "P$5") (pinfunction "5_P$5") (pintype "passive"))
      (node (ref "U1") (pin "55") (pinfunction "GPIO16/SPI_SIMO_A/TZ2_55") (pintype "bidirectional"))
      (node (ref "U5") (pin "10") (pinfunction "SDI_10") (pintype "bidirectional"))
      (node (ref "U6") (pin "10") (pinfunction "SDI_10") (pintype "bidirectional"))
    )
    (net (code "33") (name "A.SPI_SO") (class "Default")
      (node (ref "U$13") (pin "P$6") (pinfunction "6_P$6") (pintype "passive"))
      (node (ref "U1") (pin "52") (pinfunction "GPIO17/SPI_SOMI_A/TZ3_52") (pintype "bidirectional"))
      (node (ref "U5") (pin "11") (pinfunction "SDO_11") (pintype "bidirectional"))
      (node (ref "U6") (pin "11") (pinfunction "SDO_11") (pintype "bidirectional"))
    )
    (net (code "34") (name "A.VDC") (class "Default")
      (node (ref "C16") (pin "1") (pinfunction "1_1") (pintype "passive"))
      (node (ref "R8") (pin "2") (pinfunction "2_2") (pintype "passive"))
      (node (ref "R9") (pin "1") (pinfunction "1_1") (pintype "passive"))
      (node (ref "U1") (pin "16") (pinfunction "ADC_INA7_16") (pintype "input"))
    )
    (net (code "35") (name "A.V_A") (class "Default")
      (node (ref "C12") (pin "1") (pinfunction "1_1") (pintype "passive"))
      (node (ref "R12") (pin "2") (pinfunction "2_2") (pintype "passive"))
      (node (ref "R14") (pin "1") (pinfunction "1_1") (pintype "passive"))
      (node (ref "U1") (pin "29") (pinfunction "ADC_INB1_29") (pintype "input"))
    )
    (net (code "36") (name "A.V_B") (class "Default")
      (node (ref "C18") (pin "1") (pinfunction "1_1") (pintype "passive"))
      (node (ref "R16") (pin "2") (pinfunction "2_2") (pintype "passive"))
      (node (ref "R17") (pin "1") (pinfunction "1_1") (pintype "passive"))
      (node (ref "U1") (pin "21") (pinfunction "ADC_INA2/COMP1A/AIO2_21") (pintype "bidirectional"))
    )
    (net (code "37") (name "ADCINA6") (class "Default")
      (node (ref "U$12") (pin "P$2") (pinfunction "2_P$2") (pintype "passive"))
      (node (ref "U1") (pin "17") (pinfunction "ADC_INA6/COMP3A/AIO6_17") (pintype "bidirectional"))
    )
    (net (code "38") (name "AGND") (class "Default")
      (node (ref "C10") (pin "2") (pinfunction "2_2") (pintype "passive"))
      (node (ref "C11") (pin "2") (pinfunction "2_2") (pintype "passive"))
      (node (ref "C17") (pin "2") (pinfunction "2_2") (pintype "passive"))
      (node (ref "C48") (pin "2") (pinfunction "2_2") (pintype "passive"))
      (node (ref "C59") (pin "2") (pinfunction "2_2") (pintype "passive"))
      (node (ref "C61") (pin "2") (pinfunction "2_2") (pintype "passive"))
      (node (ref "R11") (pin "2") (pinfunction "2_2") (pintype "passive"))
      (node (ref "R15") (pin "2") (pinfunction "2_2") (pintype "passive"))
      (node (ref "R27") (pin "2") (pinfunction "2_2") (pintype "passive"))
      (node (ref "R31") (pin "2") (pinfunction "2_2") (pintype "passive"))
      (node (ref "R36") (pin "2") (pinfunction "2_2") (pintype "passive"))
      (node (ref "R7") (pin "2") (pinfunction "2_2") (pintype "passive"))
      (node (ref "T2") (pin "-") (pinfunction "P$2_-") (pintype "bidirectional"))
      (node (ref "T4") (pin "-") (pinfunction "P$2_-") (pintype "bidirectional"))
      (node (ref "T6") (pin "-") (pinfunction "P$2_-") (pintype "bidirectional"))
      (node (ref "U$10") (pin "P$1") (pinfunction "P$1_P$1") (pintype "bidirectional"))
      (node (ref "U$2") (pin "P$1") (pinfunction "P$1_P$1") (pintype "bidirectional"))
      (node (ref "U5") (pin "20") (pinfunction "SP3_20") (pintype "bidirectional"))
      (node (ref "U5") (pin "22") (pinfunction "SP2_22") (pintype "bidirectional"))
      (node (ref "U5") (pin "24") (pinfunction "SP1_24") (pintype "bidirectional"))
      (node (ref "U6") (pin "20") (pinfunction "SP3_20") (pintype "bidirectional"))
      (node (ref "U6") (pin "22") (pinfunction "SP2_22") (pintype "bidirectional"))
      (node (ref "U6") (pin "24") (pinfunction "SP1_24") (pintype "bidirectional"))
    )
    (net (code "39") (name "B.DC_CAL") (class "Default")
      (node (ref "U1") (pin "65") (pinfunction "GPIO53/EQEP1I/MFSXA_65") (pintype "bidirectional"))
      (node (ref "U5") (pin "47") (pinfunction "WAKE_47") (pintype "bidirectional"))
    )
    (net (code "40") (name "B.ENC_A") (class "Default")
      (node (ref "U1") (pin "69") (pinfunction "GPIO54/SPISIMOA/EQEP2A/HRCAP1_69") (pintype "bidirectional"))
      (node (ref "U4") (pin "5") (pinfunction "A4_5") (pintype "bidirectional"))
    )
    (net (code "41") (name "B.ENC_B") (class "Default")
      (node (ref "U1") (pin "75") (pinfunction "GPIO55/SPISOMIA/EQEP2B/HRCAP2_75") (pintype "bidirectional"))
      (node (ref "U4") (pin "6") (pinfunction "A5_6") (pintype "bidirectional"))
    )
    (net (code "42") (name "B.ENC_I") (class "Default")
      (node (ref "U1") (pin "85") (pinfunction "GPIO56/SPICLKA/EQEP2I/HRCAP3_85") (pintype "bidirectional"))
      (node (ref "U4") (pin "7") (pinfunction "A6_7") (pintype "bidirectional"))
    )
    (net (code "43") (name "B.EN_GATE") (class "Default")
      (node (ref "U1") (pin "53") (pinfunction "GPIO52/EQEP1S/MCLKXA/TZ3_53") (pintype "bidirectional"))
      (node (ref "U5") (pin "1") (pinfunction "EN_GATE_1") (pintype "bidirectional"))
    )
    (net (code "44") (name "B.FAULT") (class "Default")
      (node (ref "R19") (pin "2") (pinfunction "2_2") (pintype "passive"))
      (node (ref "R2") (pin "2") (pinfunction "2_2") (pintype "passive"))
      (node (ref "U1") (pin "88") (pinfunction "GPIO15/ECAP2/SCI_RXDB/SPISTEB_88") (pintype "bidirectional"))
      (node (ref "U5") (pin "8") (pinfunction "/FAULT_8") (pintype "bidirectional"))
    )
    (net (code "45") (name "B.GH_A") (class "Default")
      (node (ref "Q7") (pin "4") (pinfunction "G_4") (pintype "passive"))
      (node (ref "U5") (pin "36") (pinfunction "GH_A_36") (pintype "bidirectional"))
    )
    (net (code "46") (name "B.GH_B") (class "Default")
      (node (ref "Q9") (pin "4") (pinfunction "G_4") (pintype "passive"))
      (node (ref "U5") (pin "29") (pinfunction "GH_B_29") (pintype "bidirectional"))
    )
    (net (code "47") (name "B.GH_C") (class "Default")
      (node (ref "Q11") (pin "4") (pinfunction "G_4") (pintype "passive"))
      (node (ref "U5") (pin "28") (pinfunction "GH_C_28") (pintype "bidirectional"))
    )
    (net (code "48") (name "B.GL_A") (class "Default")
      (node (ref "Q8") (pin "4") (pinfunction "G_4") (pintype "passive"))
      (node (ref "U5") (pin "33") (pinfunction "GL_A_33") (pintype "bidirectional"))
    )
    (net (code "49") (name "B.GL_B") (class "Default")
      (node (ref "Q10") (pin "4") (pinfunction "G_4") (pintype "passive"))
      (node (ref "U5") (pin "32") (pinfunction "GL_B_32") (pintype "bidirectional"))
    )
    (net (code "50") (name "B.GL_C") (class "Default")
      (node (ref "Q12") (pin "4") (pinfunction "G_4") (pintype "passive"))
      (node (ref "U5") (pin "25") (pinfunction "GL_C_25") (pintype "bidirectional"))
    )
    (net (code "51") (name "B.I_A") (class "Default")
      (node (ref "C57") (pin "1") (pinfunction "1_1") (pintype "passive"))
      (node (ref "R26") (pin "2") (pinfunction "2_2") (pintype "passive"))
      (node (ref "U1") (pin "20") (pinfunction "ADC_INA3_20") (pintype "input"))
    )
    (net (code "52") (name "B.I_B") (class "Default")
      (node (ref "C56") (pin "1") (pinfunction "1_1") (pintype "passive"))
      (node (ref "R25") (pin "2") (pinfunction "2_2") (pintype "passive"))
      (node (ref "U1") (pin "31") (pinfunction "ADC_INB3_31") (pintype "input"))
    )
    (net (code "53") (name "B.I_C") (class "Default")
      (node (ref "C49") (pin "1") (pinfunction "1_1") (pintype "passive"))
      (node (ref "R24") (pin "2") (pinfunction "2_2") (pintype "passive"))
      (node (ref "U1") (pin "19") (pinfunction "ADC_INA4/COMP2A/AIO4_19") (pintype "bidirectional"))
    )
    (net (code "54") (name "B.PWM_AH") (class "Default")
      (node (ref "U1") (pin "58") (pinfunction "GPIO6/EPWM4A/EPWMSYNCI/EPWMSYNCO_58") (pintype "bidirectional"))
      (node (ref "U5") (pin "2") (pinfunction "INH_A_2") (pintype "bidirectional"))
    )
    (net (code "55") (name "B.PWM_AL") (class "Default")
      (node (ref "U1") (pin "57") (pinfunction "GPIO7/EPWM4B/SCIRXDA/ECAP2_57") (pintype "bidirectional"))
      (node (ref "U5") (pin "3") (pinfunction "INL_A_3") (pintype "bidirectional"))
    )
    (net (code "56") (name "B.PWM_BH") (class "Default")
      (node (ref "U1") (pin "54") (pinfunction "GPIO8/EPWM5A/ADCSOCAO_54") (pintype "bidirectional"))
      (node (ref "U5") (pin "4") (pinfunction "INH_B_4") (pintype "bidirectional"))
    )
    (net (code "57") (name "B.PWM_BL") (class "Default")
      (node (ref "U1") (pin "49") (pinfunction "GPIO9/EPWM5B/SCI_TXDB/ECAP_49") (pintype "bidirectional"))
      (node (ref "U5") (pin "5") (pinfunction "INL_B_5") (pintype "bidirectional"))
    )
    (net (code "58") (name "B.PWM_CH") (class "Default")
      (node (ref "U1") (pin "74") (pinfunction "GPIO10/EPWM6A/ADCSOCBO_74") (pintype "bidirectional"))
      (node (ref "U5") (pin "6") (pinfunction "INH_C_6") (pintype "bidirectional"))
    )
    (net (code "59") (name "B.PWM_CL") (class "Default")
      (node (ref "U1") (pin "73") (pinfunction "GPIO11/EPWM6B/SCI_RXDB/ECAP1_73") (pintype "bidirectional"))
      (node (ref "U5") (pin "7") (pinfunction "INL_C_7") (pintype "bidirectional"))
    )
    (net (code "60") (name "B.SH_A") (class "Default")
      (node (ref "Q7") (pin "1") (pinfunction "S_1") (pintype "passive"))
      (node (ref "Q7") (pin "2") (pinfunction "S_2") (pintype "passive"))
      (node (ref "Q7") (pin "3") (pinfunction "S_3") (pintype "passive"))
      (node (ref "Q8") (pin "5") (pinfunction "D_5") (pintype "passive"))
      (node (ref "Q8") (pin "6") (pinfunction "D_6") (pintype "passive"))
      (node (ref "Q8") (pin "7") (pinfunction "D_7") (pintype "passive"))
      (node (ref "Q8") (pin "8") (pinfunction "D_8") (pintype "passive"))
      (node (ref "Q8") (pin "9") (pinfunction "D_9") (pintype "passive"))
      (node (ref "R28") (pin "1") (pinfunction "1_1") (pintype "passive"))
      (node (ref "U$3") (pin "P$1") (pinfunction "P$1_P$1") (pintype "bidirectional"))
      (node (ref "U5") (pin "35") (pinfunction "SH_A_35") (pintype "bidirectional"))
    )
    (net (code "61") (name "B.SH_B") (class "Default")
      (node (ref "Q10") (pin "5") (pinfunction "D_5") (pintype "passive"))
      (node (ref "Q10") (pin "6") (pinfunction "D_6") (pintype "passive"))
      (node (ref "Q10") (pin "7") (pinfunction "D_7") (pintype "passive"))
      (node (ref "Q10") (pin "8") (pinfunction "D_8") (pintype "passive"))
      (node (ref "Q10") (pin "9") (pinfunction "D_9") (pintype "passive"))
      (node (ref "Q9") (pin "1") (pinfunction "S_1") (pintype "passive"))
      (node (ref "Q9") (pin "2") (pinfunction "S_2") (pintype "passive"))
      (node (ref "Q9") (pin "3") (pinfunction "S_3") (pintype "passive"))
      (node (ref "R32") (pin "1") (pinfunction "1_1") (pintype "passive"))
      (node (ref "U$4") (pin "P$1") (pinfunction "P$1_P$1") (pintype "bidirectional"))
      (node (ref "U5") (pin "30") (pinfunction "SH_B_30") (pintype "bidirectional"))
    )
    (net (code "62") (name "B.SH_C") (class "Default")
      (node (ref "Q11") (pin "1") (pinfunction "S_1") (pintype "passive"))
      (node (ref "Q11") (pin "2") (pinfunction "S_2") (pintype "passive"))
      (node (ref "Q11") (pin "3") (pinfunction "S_3") (pintype "passive"))
      (node (ref "Q12") (pin "5") (pinfunction "D_5") (pintype "passive"))
      (node (ref "Q12") (pin "6") (pinfunction "D_6") (pintype "passive"))
      (node (ref "Q12") (pin "7") (pinfunction "D_7") (pintype "passive"))
      (node (ref "Q12") (pin "8") (pinfunction "D_8") (pintype "passive"))
      (node (ref "Q12") (pin "9") (pinfunction "D_9") (pintype "passive"))
      (node (ref "R37") (pin "1") (pinfunction "1_1") (pintype "passive"))
      (node (ref "U$5") (pin "P$1") (pinfunction "P$1_P$1") (pintype "bidirectional"))
      (node (ref "U5") (pin "27") (pinfunction "SH_C_27") (pintype "bidirectional"))
    )
    (net (code "63") (name "B.SN1") (class "Default")
      (node (ref "C48") (pin "1") (pinfunction "1_1") (pintype "passive"))
      (node (ref "Q8") (pin "1") (pinfunction "S_1") (pintype "passive"))
      (node (ref "Q8") (pin "2") (pinfunction "S_2") (pintype "passive"))
      (node (ref "Q8") (pin "3") (pinfunction "S_3") (pintype "passive"))
      (node (ref "R27") (pin "1") (pinfunction "1_1") (pintype "passive"))
      (node (ref "U5") (pin "23") (pinfunction "SN1_23") (pintype "bidirectional"))
      (node (ref "U5") (pin "34") (pinfunction "SL_A_34") (pintype "bidirectional"))
    )
    (net (code "64") (name "B.SN2") (class "Default")
      (node (ref "C59") (pin "1") (pinfunction "1_1") (pintype "passive"))
      (node (ref "Q10") (pin "1") (pinfunction "S_1") (pintype "passive"))
      (node (ref "Q10") (pin "2") (pinfunction "S_2") (pintype "passive"))
      (node (ref "Q10") (pin "3") (pinfunction "S_3") (pintype "passive"))
      (node (ref "R31") (pin "1") (pinfunction "1_1") (pintype "passive"))
      (node (ref "U5") (pin "21") (pinfunction "SN2_21") (pintype "bidirectional"))
      (node (ref "U5") (pin "31") (pinfunction "SL_B_31") (pintype "bidirectional"))
    )
    (net (code "65") (name "B.SN3") (class "Default")
      (node (ref "C61") (pin "1") (pinfunction "1_1") (pintype "passive"))
      (node (ref "Q12") (pin "1") (pinfunction "S_1") (pintype "passive"))
      (node (ref "Q12") (pin "2") (pinfunction "S_2") (pintype "passive"))
      (node (ref "Q12") (pin "3") (pinfunction "S_3") (pintype "passive"))
      (node (ref "R36") (pin "1") (pinfunction "1_1") (pintype "passive"))
      (node (ref "U5") (pin "19") (pinfunction "SN3_19") (pintype "bidirectional"))
      (node (ref "U5") (pin "26") (pinfunction "SL_C_26") (pintype "bidirectional"))
    )
    (net (code "66") (name "B.SPI_CLK") (class "Default")
      (node (ref "U1") (pin "96") (pinfunction "GPIO14/TZ3/SCITXDB/SPICLKB_96") (pintype "bidirectional"))
    )
    (net (code "67") (name "B.SPI_CS") (class "Default")
      (node (ref "U1") (pin "43") (pinfunction "GPIO29/SCI_TXDA/SCLA/TZ3_43") (pintype "bidirectional"))
      (node (ref "U5") (pin "9") (pinfunction "/SCS_9") (pintype "bidirectional"))
    )
    (net (code "68") (name "B.SPI_SI") (class "Default")
      (node (ref "U1") (pin "97") (pinfunction "GPIO24/ECAP1/EQEP2A/SPISIMOB_97") (pintype "bidirectional"))
    )
    (net (code "69") (name "B.SPI_SO") (class "Default")
      (node (ref "U1") (pin "39") (pinfunction "GPIO25/ECAP2/EQEP2B/SPISOMIB_39") (pintype "bidirectional"))
    )
    (net (code "70") (name "B.VDC") (class "Default")
      (node (ref "C58") (pin "1") (pinfunction "1_1") (pintype "passive"))
      (node (ref "R28") (pin "2") (pinfunction "2_2") (pintype "passive"))
      (node (ref "R30") (pin "1") (pinfunction "1_1") (pintype "passive"))
      (node (ref "U1") (pin "35") (pinfunction "ADC_INB7_35") (pintype "input"))
    )
    (net (code "71") (name "B.V_A") (class "Default")
      (node (ref "C60") (pin "1") (pinfunction "1_1") (pintype "passive"))
      (node (ref "R32") (pin "2") (pinfunction "2_2") (pintype "passive"))
      (node (ref "R33") (pin "1") (pinfunction "1_1") (pintype "passive"))
      (node (ref "U1") (pin "32") (pinfunction "ADC_INB4/COMP2B/AIO12_32") (pintype "bidirectional"))
    )
    (net (code "72") (name "B.V_B") (class "Default")
      (node (ref "C62") (pin "1") (pinfunction "1_1") (pintype "passive"))
      (node (ref "R37") (pin "2") (pinfunction "2_2") (pintype "passive"))
      (node (ref "R40") (pin "1") (pinfunction "1_1") (pintype "passive"))
      (node (ref "U1") (pin "18") (pinfunction "ADC_INA5_18") (pintype "input"))
    )
    (net (code "73") (name "B.V_C") (class "Default")
      (node (ref "C38") (pin "1") (pinfunction "1_1") (pintype "passive"))
      (node (ref "R41") (pin "2") (pinfunction "2_2") (pintype "passive"))
      (node (ref "R45") (pin "1") (pinfunction "1_1") (pintype "passive"))
      (node (ref "U1") (pin "30") (pinfunction "ADC_INB2/COMP1B/AIO10_30") (pintype "bidirectional"))
      (node (ref "U1") (pin "33") (pinfunction "ADC_INB5_33") (pintype "input"))
    )
    (net (code "74") (name "CANH") (class "Default")
      (node (ref "R34") (pin "2") (pinfunction "2_2") (pintype "passive"))
      (node (ref "U$1") (pin "P$1") (pinfunction "1_P$1") (pintype "passive"))
      (node (ref "U3") (pin "P$7") (pinfunction "CANH_P$7") (pintype "bidirectional"))
    )
    (net (code "75") (name "CANL") (class "Default")
      (node (ref "R34") (pin "1") (pinfunction "1_1") (pintype "passive"))
      (node (ref "U$1") (pin "P$2") (pinfunction "2_P$2") (pintype "passive"))
      (node (ref "U3") (pin "P$6") (pinfunction "CANL_P$6") (pintype "bidirectional"))
    )
    (net (code "76") (name "EQEP1A") (class "Default")
      (node (ref "C50") (pin "1") (pinfunction "1_1") (pintype "passive"))
      (node (ref "QEP_A") (pin "P$1") (pinfunction "1_P$1") (pintype "passive"))
      (node (ref "R13") (pin "2") (pinfunction "2_2") (pintype "passive"))
      (node (ref "U4") (pin "16") (pinfunction "B1_16") (pintype "bidirectional"))
    )
    (net (code "77") (name "EQEP1B") (class "Default")
      (node (ref "C51") (pin "1") (pinfunction "1_1") (pintype "passive"))
      (node (ref "QEP_A") (pin "P$2") (pinfunction "2_P$2") (pintype "passive"))
      (node (ref "R29") (pin "2") (pinfunction "2_2") (pintype "passive"))
      (node (ref "U4") (pin "14") (pinfunction "B2_14") (pintype "bidirectional"))
    )
    (net (code "78") (name "EQEP1I") (class "Default")
      (node (ref "C52") (pin "1") (pinfunction "1_1") (pintype "passive"))
      (node (ref "QEP_A") (pin "P$3") (pinfunction "3_P$3") (pintype "passive"))
      (node (ref "R46") (pin "2") (pinfunction "2_2") (pintype "passive"))
      (node (ref "U4") (pin "13") (pinfunction "B3_13") (pintype "bidirectional"))
    )
    (net (code "79") (name "EQEP2A") (class "Default")
      (node (ref "C53") (pin "1") (pinfunction "1_1") (pintype "passive"))
      (node (ref "QEP_B") (pin "P$1") (pinfunction "1_P$1") (pintype "passive"))
      (node (ref "R47") (pin "2") (pinfunction "2_2") (pintype "passive"))
      (node (ref "U4") (pin "12") (pinfunction "B4_12") (pintype "bidirectional"))
    )
    (net (code "80") (name "EQEP2B") (class "Default")
      (node (ref "C54") (pin "1") (pinfunction "1_1") (pintype "passive"))
      (node (ref "QEP_B") (pin "P$2") (pinfunction "2_P$2") (pintype "passive"))
      (node (ref "R48") (pin "2") (pinfunction "2_2") (pintype "passive"))
      (node (ref "U4") (pin "11") (pinfunction "B5_11") (pintype "bidirectional"))
    )
    (net (code "81") (name "EQEP2I") (class "Default")
      (node (ref "C55") (pin "1") (pinfunction "1_1") (pintype "passive"))
      (node (ref "QEP_B") (pin "P$3") (pinfunction "3_P$3") (pintype "passive"))
      (node (ref "R49") (pin "2") (pinfunction "2_2") (pintype "passive"))
      (node (ref "U4") (pin "10") (pinfunction "B6_10") (pintype "bidirectional"))
    )
    (net (code "82") (name "GND") (class "Default")
      (node (ref "B1") (pin "P$1") (pinfunction "P$1_P$1") (pintype "bidirectional"))
      (node (ref "C1") (pin "2") (pinfunction "2_2") (pintype "passive"))
      (node (ref "C12") (pin "2") (pinfunction "2_2") (pintype "passive"))
      (node (ref "C13") (pin "2") (pinfunction "2_2") (pintype "passive"))
      (node (ref "C14") (pin "2") (pinfunction "2_2") (pintype "passive"))
      (node (ref "C15") (pin "2") (pinfunction "2_2") (pintype "passive"))
      (node (ref "C16") (pin "2") (pinfunction "2_2") (pintype "passive"))
      (node (ref "C18") (pin "2") (pinfunction "2_2") (pintype "passive"))
      (node (ref "C19") (pin "2") (pinfunction "2_2") (pintype "passive"))
      (node (ref "C2") (pin "2") (pinfunction "2_2") (pintype "passive"))
      (node (ref "C20") (pin "2") (pinfunction "2_2") (pintype "passive"))
      (node (ref "C21") (pin "2") (pinfunction "2_2") (pintype "passive"))
      (node (ref "C22") (pin "2") (pinfunction "2_2") (pintype "passive"))
      (node (ref "C23") (pin "2") (pinfunction "2_2") (pintype "passive"))
      (node (ref "C24") (pin "2") (pinfunction "2_2") (pintype "passive"))
      (node (ref "C25") (pin "2") (pinfunction "2_2") (pintype "passive"))
      (node (ref "C26") (pin "2") (pinfunction "2_2") (pintype "passive"))
      (node (ref "C27") (pin "2") (pinfunction "2_2") (pintype "passive"))
      (node (ref "C28") (pin "2") (pinfunction "2_2") (pintype "passive"))
      (node (ref "C29") (pin "2") (pinfunction "2_2") (pintype "passive"))
      (node (ref "C3") (pin "2") (pinfunction "2_2") (pintype "passive"))
      (node (ref "C30") (pin "2") (pinfunction "2_2") (pintype "passive"))
      (node (ref "C31") (pin "2") (pinfunction "2_2") (pintype "passive"))
      (node (ref "C32") (pin "2") (pinfunction "2_2") (pintype "passive"))
      (node (ref "C33") (pin "2") (pinfunction "2_2") (pintype "passive"))
      (node (ref "C34") (pin "2") (pinfunction "2_2") (pintype "passive"))
      (node (ref "C35") (pin "2") (pinfunction "2_2") (pintype "passive"))
      (node (ref "C36") (pin "2") (pinfunction "2_2") (pintype "passive"))
      (node (ref "C37") (pin "2") (pinfunction "2_2") (pintype "passive"))
      (node (ref "C38") (pin "2") (pinfunction "2_2") (pintype "passive"))
      (node (ref "C39") (pin "2") (pinfunction "2_2") (pintype "passive"))
      (node (ref "C4") (pin "2") (pinfunction "2_2") (pintype "passive"))
      (node (ref "C40") (pin "2") (pinfunction "2_2") (pintype "passive"))
      (node (ref "C43") (pin "2") (pinfunction "2_2") (pintype "passive"))
      (node (ref "C44") (pin "2") (pinfunction "2_2") (pintype "passive"))
      (node (ref "C45") (pin "1") (pinfunction "1_1") (pintype "passive"))
      (node (ref "C46") (pin "2") (pinfunction "2_2") (pintype "passive"))
      (node (ref "C49") (pin "2") (pinfunction "2_2") (pintype "passive"))
      (node (ref "C5") (pin "2") (pinfunction "2_2") (pintype "passive"))
      (node (ref "C50") (pin "2") (pinfunction "2_2") (pintype "passive"))
      (node (ref "C51") (pin "2") (pinfunction "2_2") (pintype "passive"))
      (node (ref "C52") (pin "2") (pinfunction "2_2") (pintype "passive"))
      (node (ref "C53") (pin "2") (pinfunction "2_2") (pintype "passive"))
      (node (ref "C54") (pin "2") (pinfunction "2_2") (pintype "passive"))
      (node (ref "C55") (pin "2") (pinfunction "2_2") (pintype "passive"))
      (node (ref "C56") (pin "2") (pinfunction "2_2") (pintype "passive"))
      (node (ref "C57") (pin "2") (pinfunction "2_2") (pintype "passive"))
      (node (ref "C58") (pin "2") (pinfunction "2_2") (pintype "passive"))
      (node (ref "C6") (pin "2") (pinfunction "2_2") (pintype "passive"))
      (node (ref "C60") (pin "2") (pinfunction "2_2") (pintype "passive"))
      (node (ref "C62") (pin "2") (pinfunction "2_2") (pintype "passive"))
      (node (ref "C63") (pin "2") (pinfunction "2_2") (pintype "passive"))
      (node (ref "C64") (pin "2") (pinfunction "2_2") (pintype "passive"))
      (node (ref "C65") (pin "2") (pinfunction "2_2") (pintype "passive"))
      (node (ref "C68") (pin "2") (pinfunction "2_2") (pintype "passive"))
      (node (ref "C69") (pin "2") (pinfunction "2_2") (pintype "passive"))
      (node (ref "C7") (pin "1") (pinfunction "1_1") (pintype "passive"))
      (node (ref "C70") (pin "2") (pinfunction "2_2") (pintype "passive"))
      (node (ref "C71") (pin "2") (pinfunction "2_2") (pintype "passive"))
      (node (ref "C72") (pin "2") (pinfunction "2_2") (pintype "passive"))
      (node (ref "C8") (pin "2") (pinfunction "2_2") (pintype "passive"))
      (node (ref "M1") (pin "P$4") (pinfunction "P$4_P$4") (pintype "bidirectional"))
      (node (ref "QEP_A") (pin "P$5") (pinfunction "5_P$5") (pintype "passive"))
      (node (ref "QEP_B") (pin "P$5") (pinfunction "5_P$5") (pintype "passive"))
      (node (ref "R1") (pin "1") (pinfunction "1_1") (pintype "passive"))
      (node (ref "R10") (pin "1") (pinfunction "1_1") (pintype "passive"))
      (node (ref "R14") (pin "2") (pinfunction "2_2") (pintype "passive"))
      (node (ref "R17") (pin "2") (pinfunction "2_2") (pintype "passive"))
      (node (ref "R30") (pin "2") (pinfunction "2_2") (pintype "passive"))
      (node (ref "R33") (pin "2") (pinfunction "2_2") (pintype "passive"))
      (node (ref "R40") (pin "2") (pinfunction "2_2") (pintype "passive"))
      (node (ref "R42") (pin "2") (pinfunction "2_2") (pintype "passive"))
      (node (ref "R45") (pin "2") (pinfunction "2_2") (pintype "passive"))
      (node (ref "R9") (pin "2") (pinfunction "2_2") (pintype "passive"))
      (node (ref "U$11") (pin "P$1") (pinfunction "1_P$1") (pintype "passive"))
      (node (ref "U$12") (pin "P$3") (pinfunction "3_P$3") (pintype "passive"))
      (node (ref "U$13") (pin "P$2") (pinfunction "2_P$2") (pintype "passive"))
      (node (ref "U$2") (pin "P$2") (pinfunction "P$2_P$2") (pintype "bidirectional"))
      (node (ref "U1") (pin "15") (pinfunction "VSS2_15") (pintype "power_in"))
      (node (ref "U1") (pin "26") (pinfunction "VSSA_26") (pintype "power_in"))
      (node (ref "U1") (pin "27") (pinfunction "VREFLO_27") (pintype "input"))
      (node (ref "U1") (pin "36") (pinfunction "VSS3_36") (pintype "power_in"))
      (node (ref "U1") (pin "4") (pinfunction "VSS1_4") (pintype "power_in"))
      (node (ref "U1") (pin "47") (pinfunction "VSS4_47") (pintype "power_in"))
      (node (ref "U1") (pin "62") (pinfunction "VSS5_62") (pintype "power_in"))
      (node (ref "U1") (pin "80") (pinfunction "VSS6_80") (pintype "power_in"))
      (node (ref "U1") (pin "90") (pinfunction "~{VREGENZ}_90") (pintype "input"))
      (node (ref "U1") (pin "92") (pinfunction "VSS7_92") (pintype "power_in"))
      (node (ref "U2") (pin "2") (pinfunction "GND_2") (pintype "bidirectional"))
      (node (ref "U3") (pin "P$2") (pinfunction "GND_P$2") (pintype "bidirectional"))
      (node (ref "U4") (pin "9") (pinfunction "GND_9") (pintype "passive"))
      (node (ref "U5") (pin "14") (pinfunction "GND14_14") (pintype "bidirectional"))
      (node (ref "U5") (pin "45") (pinfunction "GND45_45") (pintype "bidirectional"))
      (node (ref "U5") (pin "49") (pinfunction "PAD_49") (pintype "bidirectional"))
      (node (ref "U6") (pin "14") (pinfunction "GND14_14") (pintype "bidirectional"))
      (node (ref "U6") (pin "45") (pinfunction "GND45_45") (pintype "bidirectional"))
      (node (ref "U6") (pin "49") (pinfunction "PAD_49") (pintype "bidirectional"))
      (node (ref "U7") (pin "P$7") (pinfunction "GND_P$7") (pintype "bidirectional"))
      (node (ref "U8") (pin "2") (pinfunction "GND_2") (pintype "passive"))
    )
    (net (code "83") (name "GPIO22") (class "Default")
      (node (ref "U1") (pin "98") (pinfunction "GPIO22/EQEP1S/MCLKXA/SCITXDB_98") (pintype "bidirectional"))
    )
    (net (code "84") (name "GPIO30") (class "Default")
      (node (ref "R44") (pin "2") (pinfunction "2_2") (pintype "passive"))
      (node (ref "U1") (pin "41") (pinfunction "GPIO30/CAN_RXA/EQEP2I/EPWM7A_41") (pintype "bidirectional"))
    )
    (net (code "85") (name "GPIO31") (class "Default")
      (node (ref "R43") (pin "2") (pinfunction "2_2") (pintype "passive"))
      (node (ref "U1") (pin "40") (pinfunction "GPIO31/CAN_TXA/EQEP2S/EPWM8A_40") (pintype "bidirectional"))
    )
    (net (code "86") (name "GPIO32") (class "Default")
      (node (ref "U$13") (pin "P$4") (pinfunction "4_P$4") (pintype "passive"))
      (node (ref "U1") (pin "99") (pinfunction "GPIO32/SDA_A/EPWMSYNCI/ADCSOCAO_99") (pintype "bidirectional"))
    )
    (net (code "87") (name "GPIO33") (class "Default")
      (node (ref "U$13") (pin "P$3") (pinfunction "3_P$3") (pintype "passive"))
      (node (ref "U1") (pin "100") (pinfunction "GPIO33/SCL_A/EPWMSYNCO/ADCSOCBO_100") (pintype "bidirectional"))
    )
    (net (code "88") (name "GPIO34") (class "Default")
      (node (ref "U1") (pin "68") (pinfunction "GPIO34/COMP2OUT/COMP3OUT_68") (pintype "bidirectional"))
      (node (ref "U2") (pin "1") (pinfunction "1A_1") (pintype "bidirectional"))
    )
    (net (code "89") (name "GPIO39") (class "Default")
      (node (ref "U1") (pin "66") (pinfunction "GPIO39_66") (pintype "bidirectional"))
      (node (ref "U2") (pin "3") (pinfunction "2A_3") (pintype "bidirectional"))
    )
    (net (code "90") (name "GPIO40") (class "Default")
      (node (ref "U1") (pin "82") (pinfunction "GPIO40/EPWM7A/SCI_TXDB_82") (pintype "bidirectional"))
    )
    (net (code "91") (name "GPIO41") (class "Default")
      (node (ref "U1") (pin "76") (pinfunction "GPIO41/EPWM7B/SCI_RXDB_76") (pintype "bidirectional"))
    )
    (net (code "92") (name "GPIO42") (class "Default")
      (node (ref "U1") (pin "1") (pinfunction "GPIO42/EPWM8A/~{TZ1}/COMP1OUT_1") (pintype "bidirectional"))
    )
    (net (code "93") (name "GPIO43") (class "Default")
      (node (ref "U$13") (pin "P$8") (pinfunction "8_P$8") (pintype "passive"))
      (node (ref "U1") (pin "8") (pinfunction "GPIO43/EPWM8B/~{TZ2}/COMP2OUT_8") (pintype "bidirectional"))
    )
    (net (code "94") (name "GPIO44") (class "Default")
      (node (ref "U1") (pin "56") (pinfunction "GPIO44/MFSRA/SCIRXDB/EPWM7B_56") (pintype "bidirectional"))
    )
    (net (code "95") (name "GPIO57") (class "Default")
      (node (ref "U1") (pin "89") (pinfunction "GPIO57/SPISTEA/EQEP2S/HRCAP4_89") (pintype "bidirectional"))
    )
    (net (code "96") (name "GPIO58") (class "Default")
      (node (ref "U1") (pin "94") (pinfunction "GPIO58/MCLKRA/SCI_TXDB/EPWM7A_94") (pintype "bidirectional"))
    )
    (net (code "97") (name "Net-(D1-PadC)") (class "Default")
      (node (ref "D1") (pin "C") (pinfunction "C_C") (pintype "passive"))
      (node (ref "R1") (pin "2") (pinfunction "2_2") (pintype "passive"))
    )
    (net (code "98") (name "Net-(D2-PadC)") (class "Default")
      (node (ref "D2") (pin "C") (pinfunction "C_C") (pintype "passive"))
      (node (ref "R22") (pin "1") (pinfunction "1_1") (pintype "passive"))
    )
    (net (code "99") (name "Net-(D3-PadC)") (class "Default")
      (node (ref "D3") (pin "C") (pinfunction "C_C") (pintype "passive"))
      (node (ref "R19") (pin "1") (pinfunction "1_1") (pintype "passive"))
    )
    (net (code "100") (name "Net-(D4-PadC)") (class "Default")
      (node (ref "D4") (pin "C") (pinfunction "C_C") (pintype "passive"))
      (node (ref "R38") (pin "2") (pinfunction "2_2") (pintype "passive"))
    )
    (net (code "101") (name "Net-(D5-PadC)") (class "Default")
      (node (ref "D5") (pin "C") (pinfunction "C_C") (pintype "passive"))
      (node (ref "R39") (pin "2") (pinfunction "2_2") (pintype "passive"))
    )
    (net (code "102") (name "Net-(T1-P$2)") (class "Default")
      (node (ref "T1") (pin "-") (pinfunction "P$2_-") (pintype "bidirectional"))
      (node (ref "T2") (pin "+") (pinfunction "P$1_+") (pintype "bidirectional"))
    )
    (net (code "103") (name "Net-(T3-P$2)") (class "Default")
      (node (ref "T3") (pin "-") (pinfunction "P$2_-") (pintype "bidirectional"))
      (node (ref "T4") (pin "+") (pinfunction "P$1_+") (pintype "bidirectional"))
    )
    (net (code "104") (name "Net-(T5-P$2)") (class "Default")
      (node (ref "T5") (pin "-") (pinfunction "P$2_-") (pintype "bidirectional"))
      (node (ref "T6") (pin "+") (pinfunction "P$1_+") (pintype "bidirectional"))
    )
    (net (code "105") (name "Net-(U$12-4)") (class "Default")
      (node (ref "U$12") (pin "P$4") (pinfunction "4_P$4") (pintype "passive"))
      (node (ref "U1") (pin "34") (pinfunction "ADC_INB6/COMP3B/AIO14_34") (pintype "bidirectional"))
    )
    (net (code "106") (name "Net-(U1C-VDD1)") (class "Default")
      (node (ref "C1") (pin "1") (pinfunction "1_1") (pintype "passive"))
      (node (ref "U1") (pin "3") (pinfunction "VDD1_3") (pintype "power_in"))
    )
    (net (code "107") (name "Net-(U1C-VDD2)") (class "Default")
      (node (ref "C2") (pin "1") (pinfunction "1_1") (pintype "passive"))
      (node (ref "U1") (pin "14") (pinfunction "VDD2_14") (pintype "power_in"))
    )
    (net (code "108") (name "Net-(U1C-VDD3)") (class "Default")
      (node (ref "C22") (pin "1") (pinfunction "1_1") (pintype "passive"))
      (node (ref "U1") (pin "37") (pinfunction "VDD3_37") (pintype "power_in"))
    )
    (net (code "109") (name "Net-(U1C-VDD4)") (class "Default")
      (node (ref "C23") (pin "1") (pinfunction "1_1") (pintype "passive"))
      (node (ref "U1") (pin "63") (pinfunction "VDD4_63") (pintype "power_in"))
    )
    (net (code "110") (name "Net-(U1C-VDD5)") (class "Default")
      (node (ref "C5") (pin "1") (pinfunction "1_1") (pintype "passive"))
      (node (ref "U1") (pin "81") (pinfunction "VDD5_81") (pintype "power_in"))
    )
    (net (code "111") (name "Net-(U1C-VDD6)") (class "Default")
      (node (ref "C6") (pin "1") (pinfunction "1_1") (pintype "passive"))
      (node (ref "U1") (pin "91") (pinfunction "VDD6_91") (pintype "power_in"))
    )
    (net (code "112") (name "Net-(U1C-VDDA)") (class "Default")
      (node (ref "C19") (pin "1") (pinfunction "1_1") (pintype "passive"))
      (node (ref "L1") (pin "1") (pinfunction "1_1") (pintype "passive"))
      (node (ref "U1") (pin "25") (pinfunction "VDDA_25") (pintype "power_in"))
    )
    (net (code "113") (name "Net-(U1C-VDDIO1)") (class "Default")
      (node (ref "C20") (pin "1") (pinfunction "1_1") (pintype "passive"))
      (node (ref "C26") (pin "1") (pinfunction "1_1") (pintype "passive"))
      (node (ref "C27") (pin "1") (pinfunction "1_1") (pintype "passive"))
      (node (ref "C28") (pin "1") (pinfunction "1_1") (pintype "passive"))
      (node (ref "C29") (pin "1") (pinfunction "1_1") (pintype "passive"))
      (node (ref "C30") (pin "1") (pinfunction "1_1") (pintype "passive"))
      (node (ref "L2") (pin "1") (pinfunction "1_1") (pintype "passive"))
      (node (ref "U1") (pin "13") (pinfunction "VDDIO2_13") (pintype "power_in"))
      (node (ref "U1") (pin "38") (pinfunction "VDDIO3_38") (pintype "power_in"))
      (node (ref "U1") (pin "5") (pinfunction "VDDIO1_5") (pintype "power_in"))
      (node (ref "U1") (pin "61") (pinfunction "VDDIO4_61") (pintype "power_in"))
      (node (ref "U1") (pin "79") (pinfunction "VDDIO5_79") (pintype "power_in"))
      (node (ref "U1") (pin "93") (pinfunction "VDDIO6_93") (pintype "power_in"))
    )
    (net (code "114") (name "Net-(U2-1Y)") (class "Default")
      (node (ref "R38") (pin "1") (pinfunction "1_1") (pintype "passive"))
      (node (ref "U2") (pin "6") (pinfunction "1Y_6") (pintype "bidirectional"))
    )
    (net (code "115") (name "Net-(U2-2Y)") (class "Default")
      (node (ref "R39") (pin "1") (pinfunction "1_1") (pintype "passive"))
      (node (ref "U2") (pin "4") (pinfunction "2Y_4") (pintype "bidirectional"))
    )
    (net (code "116") (name "Net-(U3-D)") (class "Default")
      (node (ref "R43") (pin "1") (pinfunction "1_1") (pintype "passive"))
      (node (ref "U3") (pin "P$1") (pinfunction "D_P$1") (pintype "bidirectional"))
    )
    (net (code "117") (name "Net-(U3-EN)") (class "Default")
      (node (ref "R35") (pin "1") (pinfunction "1_1") (pintype "passive"))
      (node (ref "U3") (pin "P$5") (pinfunction "EN_P$5") (pintype "bidirectional"))
    )
    (net (code "118") (name "Net-(U3-R)") (class "Default")
      (node (ref "R44") (pin "1") (pinfunction "1_1") (pintype "passive"))
      (node (ref "U3") (pin "P$4") (pinfunction "R_P$4") (pintype "bidirectional"))
    )
    (net (code "119") (name "Net-(U3-RS)") (class "Default")
      (node (ref "R42") (pin "1") (pinfunction "1_1") (pintype "passive"))
      (node (ref "U3") (pin "P$8") (pinfunction "RS_P$8") (pintype "bidirectional"))
    )
    (net (code "120") (name "Net-(U4-OE)") (class "Default")
      (node (ref "R18") (pin "2") (pinfunction "2_2") (pintype "passive"))
      (node (ref "U4") (pin "8") (pinfunction "OE_8") (pintype "input"))
    )
    (net (code "121") (name "Net-(U5-AVDD)") (class "Default")
      (node (ref "C43") (pin "1") (pinfunction "1_1") (pintype "passive"))
      (node (ref "U5") (pin "15") (pinfunction "AVDD_15") (pintype "bidirectional"))
    )
    (net (code "122") (name "Net-(U5-CP1H)") (class "Default")
      (node (ref "C66") (pin "1") (pinfunction "1_1") (pintype "passive"))
      (node (ref "U5") (pin "43") (pinfunction "CP1H_43") (pintype "bidirectional"))
    )
    (net (code "123") (name "Net-(U5-CP1L)") (class "Default")
      (node (ref "C66") (pin "2") (pinfunction "2_2") (pintype "passive"))
      (node (ref "U5") (pin "42") (pinfunction "CP1L_42") (pintype "bidirectional"))
    )
    (net (code "124") (name "Net-(U5-CP2H)") (class "Default")
      (node (ref "C67") (pin "1") (pinfunction "1_1") (pintype "passive"))
      (node (ref "U5") (pin "39") (pinfunction "CP2H_39") (pintype "bidirectional"))
    )
    (net (code "125") (name "Net-(U5-CP2L)") (class "Default")
      (node (ref "C67") (pin "2") (pinfunction "2_2") (pintype "passive"))
      (node (ref "U5") (pin "40") (pinfunction "CP2L_40") (pintype "bidirectional"))
    )
    (net (code "126") (name "Net-(U5-DVDD)") (class "Default")
      (node (ref "C44") (pin "1") (pinfunction "1_1") (pintype "passive"))
      (node (ref "U5") (pin "46") (pinfunction "DVDD_46") (pintype "bidirectional"))
    )
    (net (code "127") (name "Net-(U5-SO1)") (class "Default")
      (node (ref "R26") (pin "1") (pinfunction "1_1") (pintype "passive"))
      (node (ref "U5") (pin "16") (pinfunction "SO1_16") (pintype "bidirectional"))
    )
    (net (code "128") (name "Net-(U5-SO2)") (class "Default")
      (node (ref "R25") (pin "1") (pinfunction "1_1") (pintype "passive"))
      (node (ref "U5") (pin "17") (pinfunction "SO2_17") (pintype "bidirectional"))
    )
    (net (code "129") (name "Net-(U5-SO3)") (class "Default")
      (node (ref "R24") (pin "1") (pinfunction "1_1") (pintype "passive"))
      (node (ref "U5") (pin "18") (pinfunction "SO3_18") (pintype "bidirectional"))
    )
    (net (code "130") (name "Net-(U5-VCPH)") (class "Default")
      (node (ref "C47") (pin "1") (pinfunction "1_1") (pintype "passive"))
      (node (ref "U5") (pin "38") (pinfunction "VCPH_38") (pintype "bidirectional"))
    )
    (net (code "131") (name "Net-(U5-VCP_LSD)") (class "Default")
      (node (ref "C46") (pin "1") (pinfunction "1_1") (pintype "passive"))
      (node (ref "U5") (pin "37") (pinfunction "VCP_LSD_37") (pintype "bidirectional"))
    )
    (net (code "132") (name "Net-(U5-VDRAIN)") (class "Default")
      (node (ref "R20") (pin "2") (pinfunction "2_2") (pintype "passive"))
      (node (ref "U5") (pin "44") (pinfunction "VDRAIN_44") (pintype "bidirectional"))
    )
    (net (code "133") (name "Net-(U5-VREG)") (class "Default")
      (node (ref "C32") (pin "1") (pinfunction "1_1") (pintype "passive"))
      (node (ref "U5") (pin "48") (pinfunction "VREG_48") (pintype "bidirectional"))
    )
    (net (code "134") (name "Net-(U6-AVDD)") (class "Default")
      (node (ref "C3") (pin "1") (pinfunction "1_1") (pintype "passive"))
      (node (ref "U6") (pin "15") (pinfunction "AVDD_15") (pintype "bidirectional"))
    )
    (net (code "135") (name "Net-(U6-CP1H)") (class "Default")
      (node (ref "C41") (pin "1") (pinfunction "1_1") (pintype "passive"))
      (node (ref "U6") (pin "43") (pinfunction "CP1H_43") (pintype "bidirectional"))
    )
    (net (code "136") (name "Net-(U6-CP1L)") (class "Default")
      (node (ref "C41") (pin "2") (pinfunction "2_2") (pintype "passive"))
      (node (ref "U6") (pin "42") (pinfunction "CP1L_42") (pintype "bidirectional"))
    )
    (net (code "137") (name "Net-(U6-CP2H)") (class "Default")
      (node (ref "C42") (pin "1") (pinfunction "1_1") (pintype "passive"))
      (node (ref "U6") (pin "39") (pinfunction "CP2H_39") (pintype "bidirectional"))
    )
    (net (code "138") (name "Net-(U6-CP2L)") (class "Default")
      (node (ref "C42") (pin "2") (pinfunction "2_2") (pintype "passive"))
      (node (ref "U6") (pin "40") (pinfunction "CP2L_40") (pintype "bidirectional"))
    )
    (net (code "139") (name "Net-(U6-DVDD)") (class "Default")
      (node (ref "C4") (pin "1") (pinfunction "1_1") (pintype "passive"))
      (node (ref "U6") (pin "46") (pinfunction "DVDD_46") (pintype "bidirectional"))
    )
    (net (code "140") (name "Net-(U6-SO1)") (class "Default")
      (node (ref "R5") (pin "1") (pinfunction "1_1") (pintype "passive"))
      (node (ref "U6") (pin "16") (pinfunction "SO1_16") (pintype "bidirectional"))
    )
    (net (code "141") (name "Net-(U6-SO2)") (class "Default")
      (node (ref "R4") (pin "1") (pinfunction "1_1") (pintype "passive"))
      (node (ref "U6") (pin "17") (pinfunction "SO2_17") (pintype "bidirectional"))
    )
    (net (code "142") (name "Net-(U6-SO3)") (class "Default")
      (node (ref "R3") (pin "1") (pinfunction "1_1") (pintype "passive"))
      (node (ref "U6") (pin "18") (pinfunction "SO3_18") (pintype "bidirectional"))
    )
    (net (code "143") (name "Net-(U6-VCPH)") (class "Default")
      (node (ref "C9") (pin "1") (pinfunction "1_1") (pintype "passive"))
      (node (ref "U6") (pin "38") (pinfunction "VCPH_38") (pintype "bidirectional"))
    )
    (net (code "144") (name "Net-(U6-VCP_LSD)") (class "Default")
      (node (ref "C8") (pin "1") (pinfunction "1_1") (pintype "passive"))
      (node (ref "U6") (pin "37") (pinfunction "VCP_LSD_37") (pintype "bidirectional"))
    )
    (net (code "145") (name "Net-(U6-VDRAIN)") (class "Default")
      (node (ref "R21") (pin "2") (pinfunction "2_2") (pintype "passive"))
      (node (ref "U6") (pin "44") (pinfunction "VDRAIN_44") (pintype "bidirectional"))
    )
    (net (code "146") (name "Net-(U6-VREG)") (class "Default")
      (node (ref "C31") (pin "1") (pinfunction "1_1") (pintype "passive"))
      (node (ref "U6") (pin "48") (pinfunction "VREG_48") (pintype "bidirectional"))
    )
    (net (code "147") (name "Net-(U7-LX)") (class "Default")
      (node (ref "I1") (pin "P$1") (pinfunction "P$1_P$1") (pintype "bidirectional"))
      (node (ref "U7") (pin "P$8") (pinfunction "LX_P$8") (pintype "bidirectional"))
    )
    (net (code "148") (name "Net-(U7-VCC)") (class "Default")
      (node (ref "C69") (pin "1") (pinfunction "1_1") (pintype "passive"))
      (node (ref "U7") (pin "P$3") (pinfunction "VCC_P$3") (pintype "bidirectional"))
    )
    (net (code "149") (name "RESET#") (class "Default")
      (node (ref "B1") (pin "P$2") (pinfunction "P$2_P$2") (pintype "bidirectional"))
      (node (ref "C39") (pin "1") (pinfunction "1_1") (pintype "passive"))
      (node (ref "R6") (pin "1") (pinfunction "1_1") (pintype "passive"))
      (node (ref "U1") (pin "11") (pinfunction "~{XRS}_11") (pintype "bidirectional"))
      (node (ref "U5") (pin "13") (pinfunction "PWRGD_13") (pintype "bidirectional"))
      (node (ref "U6") (pin "13") (pinfunction "PWRGD_13") (pintype "bidirectional"))
    )
    (net (code "150") (name "SPICLKB") (class "Default")
      (node (ref "U$11") (pin "P$3") (pinfunction "3_P$3") (pintype "passive"))
      (node (ref "U1") (pin "78") (pinfunction "GPIO26/ECAP3/EQEP2I/SPICLKB/USB0DP_78") (pintype "bidirectional"))
    )
    (net (code "151") (name "SPISIMOB") (class "Default")
      (node (ref "U$11") (pin "P$5") (pinfunction "5_P$5") (pintype "passive"))
      (node (ref "U1") (pin "44") (pinfunction "GPIO12/TZ1/SCITXDA/SPISIMOB_44") (pintype "bidirectional"))
    )
    (net (code "152") (name "SPISOMIB") (class "Default")
      (node (ref "U$11") (pin "P$2") (pinfunction "2_P$2") (pintype "passive"))
      (node (ref "U1") (pin "95") (pinfunction "GPIO13/TZ2/SPISOMIB_95") (pintype "bidirectional"))
    )
    (net (code "153") (name "SPISTEB") (class "Default")
      (node (ref "U$11") (pin "P$4") (pinfunction "4_P$4") (pintype "passive"))
      (node (ref "U1") (pin "77") (pinfunction "GPIO27/HRCAP2/EQEP2S/SPISTEB/USB0DM_77") (pintype "bidirectional"))
    )
    (net (code "154") (name "TCK") (class "Default")
      (node (ref "M1") (pin "P$3") (pinfunction "P$3_P$3") (pintype "bidirectional"))
      (node (ref "U1") (pin "67") (pinfunction "TCK/GPIO38_67") (pintype "input"))
    )
    (net (code "155") (name "TDI") (class "Default")
      (node (ref "M1") (pin "P$7") (pinfunction "P$7_P$7") (pintype "bidirectional"))
      (node (ref "U1") (pin "71") (pinfunction "TDI/GPIO35_71") (pintype "input"))
    )
    (net (code "156") (name "TDO") (class "Default")
      (node (ref "M1") (pin "P$8") (pinfunction "P$8_P$8") (pintype "bidirectional"))
      (node (ref "U1") (pin "70") (pinfunction "TDO/GPIO37_70") (pintype "output"))
    )
    (net (code "157") (name "TMS") (class "Default")
      (node (ref "M1") (pin "P$5") (pinfunction "P$5_P$5") (pintype "bidirectional"))
      (node (ref "U1") (pin "72") (pinfunction "TMS/GPIO36_72") (pintype "input"))
    )
    (net (code "158") (name "TRST") (class "Default")
      (node (ref "M1") (pin "P$1") (pinfunction "P$1_P$1") (pintype "bidirectional"))
      (node (ref "R10") (pin "2") (pinfunction "2_2") (pintype "passive"))
      (node (ref "U1") (pin "12") (pinfunction "~{TRST}_12") (pintype "input"))
    )
    (net (code "159") (name "VDD") (class "Default")
      (node (ref "C25") (pin "1") (pinfunction "1_1") (pintype "passive"))
      (node (ref "C33") (pin "1") (pinfunction "1_1") (pintype "passive"))
      (node (ref "C34") (pin "1") (pinfunction "1_1") (pintype "passive"))
      (node (ref "C45") (pin "2") (pinfunction "2_2") (pintype "passive"))
      (node (ref "C47") (pin "2") (pinfunction "2_2") (pintype "passive"))
      (node (ref "C63") (pin "1") (pinfunction "1_1") (pintype "passive"))
      (node (ref "C64") (pin "1") (pinfunction "1_1") (pintype "passive"))
      (node (ref "C65") (pin "1") (pinfunction "1_1") (pintype "passive"))
      (node (ref "C68") (pin "1") (pinfunction "1_1") (pintype "passive"))
      (node (ref "C7") (pin "2") (pinfunction "2_2") (pintype "passive"))
      (node (ref "C9") (pin "2") (pinfunction "2_2") (pintype "passive"))
      (node (ref "Q1") (pin "5") (pinfunction "D_5") (pintype "passive"))
      (node (ref "Q1") (pin "6") (pinfunction "D_6") (pintype "passive"))
      (node (ref "Q1") (pin "7") (pinfunction "D_7") (pintype "passive"))
      (node (ref "Q1") (pin "8") (pinfunction "D_8") (pintype "passive"))
      (node (ref "Q1") (pin "9") (pinfunction "D_9") (pintype "passive"))
      (node (ref "Q11") (pin "5") (pinfunction "D_5") (pintype "passive"))
      (node (ref "Q11") (pin "6") (pinfunction "D_6") (pintype "passive"))
      (node (ref "Q11") (pin "7") (pinfunction "D_7") (pintype "passive"))
      (node (ref "Q11") (pin "8") (pinfunction "D_8") (pintype "passive"))
      (node (ref "Q11") (pin "9") (pinfunction "D_9") (pintype "passive"))
      (node (ref "Q2") (pin "5") (pinfunction "D_5") (pintype "passive"))
      (node (ref "Q2") (pin "6") (pinfunction "D_6") (pintype "passive"))
      (node (ref "Q2") (pin "7") (pinfunction "D_7") (pintype "passive"))
      (node (ref "Q2") (pin "8") (pinfunction "D_8") (pintype "passive"))
      (node (ref "Q2") (pin "9") (pinfunction "D_9") (pintype "passive"))
      (node (ref "Q3") (pin "5") (pinfunction "D_5") (pintype "passive"))
      (node (ref "Q3") (pin "6") (pinfunction "D_6") (pintype "passive"))
      (node (ref "Q3") (pin "7") (pinfunction "D_7") (pintype "passive"))
      (node (ref "Q3") (pin "8") (pinfunction "D_8") (pintype "passive"))
      (node (ref "Q3") (pin "9") (pinfunction "D_9") (pintype "passive"))
      (node (ref "Q7") (pin "5") (pinfunction "D_5") (pintype "passive"))
      (node (ref "Q7") (pin "6") (pinfunction "D_6") (pintype "passive"))
      (node (ref "Q7") (pin "7") (pinfunction "D_7") (pintype "passive"))
      (node (ref "Q7") (pin "8") (pinfunction "D_8") (pintype "passive"))
      (node (ref "Q7") (pin "9") (pinfunction "D_9") (pintype "passive"))
      (node (ref "Q9") (pin "5") (pinfunction "D_5") (pintype "passive"))
      (node (ref "Q9") (pin "6") (pinfunction "D_6") (pintype "passive"))
      (node (ref "Q9") (pin "7") (pinfunction "D_7") (pintype "passive"))
      (node (ref "Q9") (pin "8") (pinfunction "D_8") (pintype "passive"))
      (node (ref "Q9") (pin "9") (pinfunction "D_9") (pintype "passive"))
      (node (ref "R20") (pin "1") (pinfunction "1_1") (pintype "passive"))
      (node (ref "R21") (pin "1") (pinfunction "1_1") (pintype "passive"))
      (node (ref "R41") (pin "1") (pinfunction "1_1") (pintype "passive"))
      (node (ref "T1") (pin "+") (pinfunction "P$1_+") (pintype "bidirectional"))
      (node (ref "T3") (pin "+") (pinfunction "P$1_+") (pintype "bidirectional"))
      (node (ref "T5") (pin "+") (pinfunction "P$1_+") (pintype "bidirectional"))
      (node (ref "U$9") (pin "P$1") (pinfunction "P$1_P$1") (pintype "bidirectional"))
      (node (ref "U5") (pin "41") (pinfunction "PVDD_41") (pintype "bidirectional"))
      (node (ref "U6") (pin "41") (pinfunction "PVDD_41") (pintype "bidirectional"))
      (node (ref "U7") (pin "P$1") (pinfunction "VIN_P$1") (pintype "bidirectional"))
      (node (ref "U7") (pin "P$2") (pinfunction "EN_P$2") (pintype "bidirectional"))
    )
    (net (code "160") (name "unconnected-(M1-PadP$6)") (class "Default")
      (node (ref "M1") (pin "P$6") (pinfunction "P$6_P$6") (pintype "bidirectional"))
    )
    (net (code "161") (name "unconnected-(U1A-TEST2-Pad45)") (class "Default")
      (node (ref "U1") (pin "45") (pinfunction "TEST2_45") (pintype "output"))
    )
    (net (code "162") (name "unconnected-(U1A-VREFHI-Pad24)") (class "Default")
      (node (ref "U1") (pin "24") (pinfunction "VREFHI_24") (pintype "input"))
    )
    (net (code "163") (name "unconnected-(U1A-X1-Pad60)") (class "Default")
      (node (ref "U1") (pin "60") (pinfunction "X1_60") (pintype "input"))
    )
    (net (code "164") (name "unconnected-(U1A-X2-Pad59)") (class "Default")
      (node (ref "U1") (pin "59") (pinfunction "X2_59") (pintype "output"))
    )
    (net (code "165") (name "unconnected-(U7-MODE-PadP$5)") (class "Default")
      (node (ref "U7") (pin "P$5") (pinfunction "MODE_P$5") (pintype "bidirectional"))
    )
    (net (code "166") (name "unconnected-(U7-~{RST}-PadP$6)") (class "Default")
      (node (ref "U7") (pin "P$6") (pinfunction "~{RST}_P$6") (pintype "bidirectional"))
    )
    (net (code "167") (name "unconnected-(U8-NC-Pad5)") (class "Default")
      (node (ref "U8") (pin "5") (pinfunction "NC_5") (pintype "no_connect"))
    )
    (net (code "168") (name "unconnected-(U8-NC_2-Pad4)") (class "Default")
      (node (ref "U8") (pin "4") (pinfunction "NC_2_4") (pintype "no_connect"))
    )
  )
)
